# octanis_eps_v05.net
KiCad netlist of a schematic drawn in EAGLE
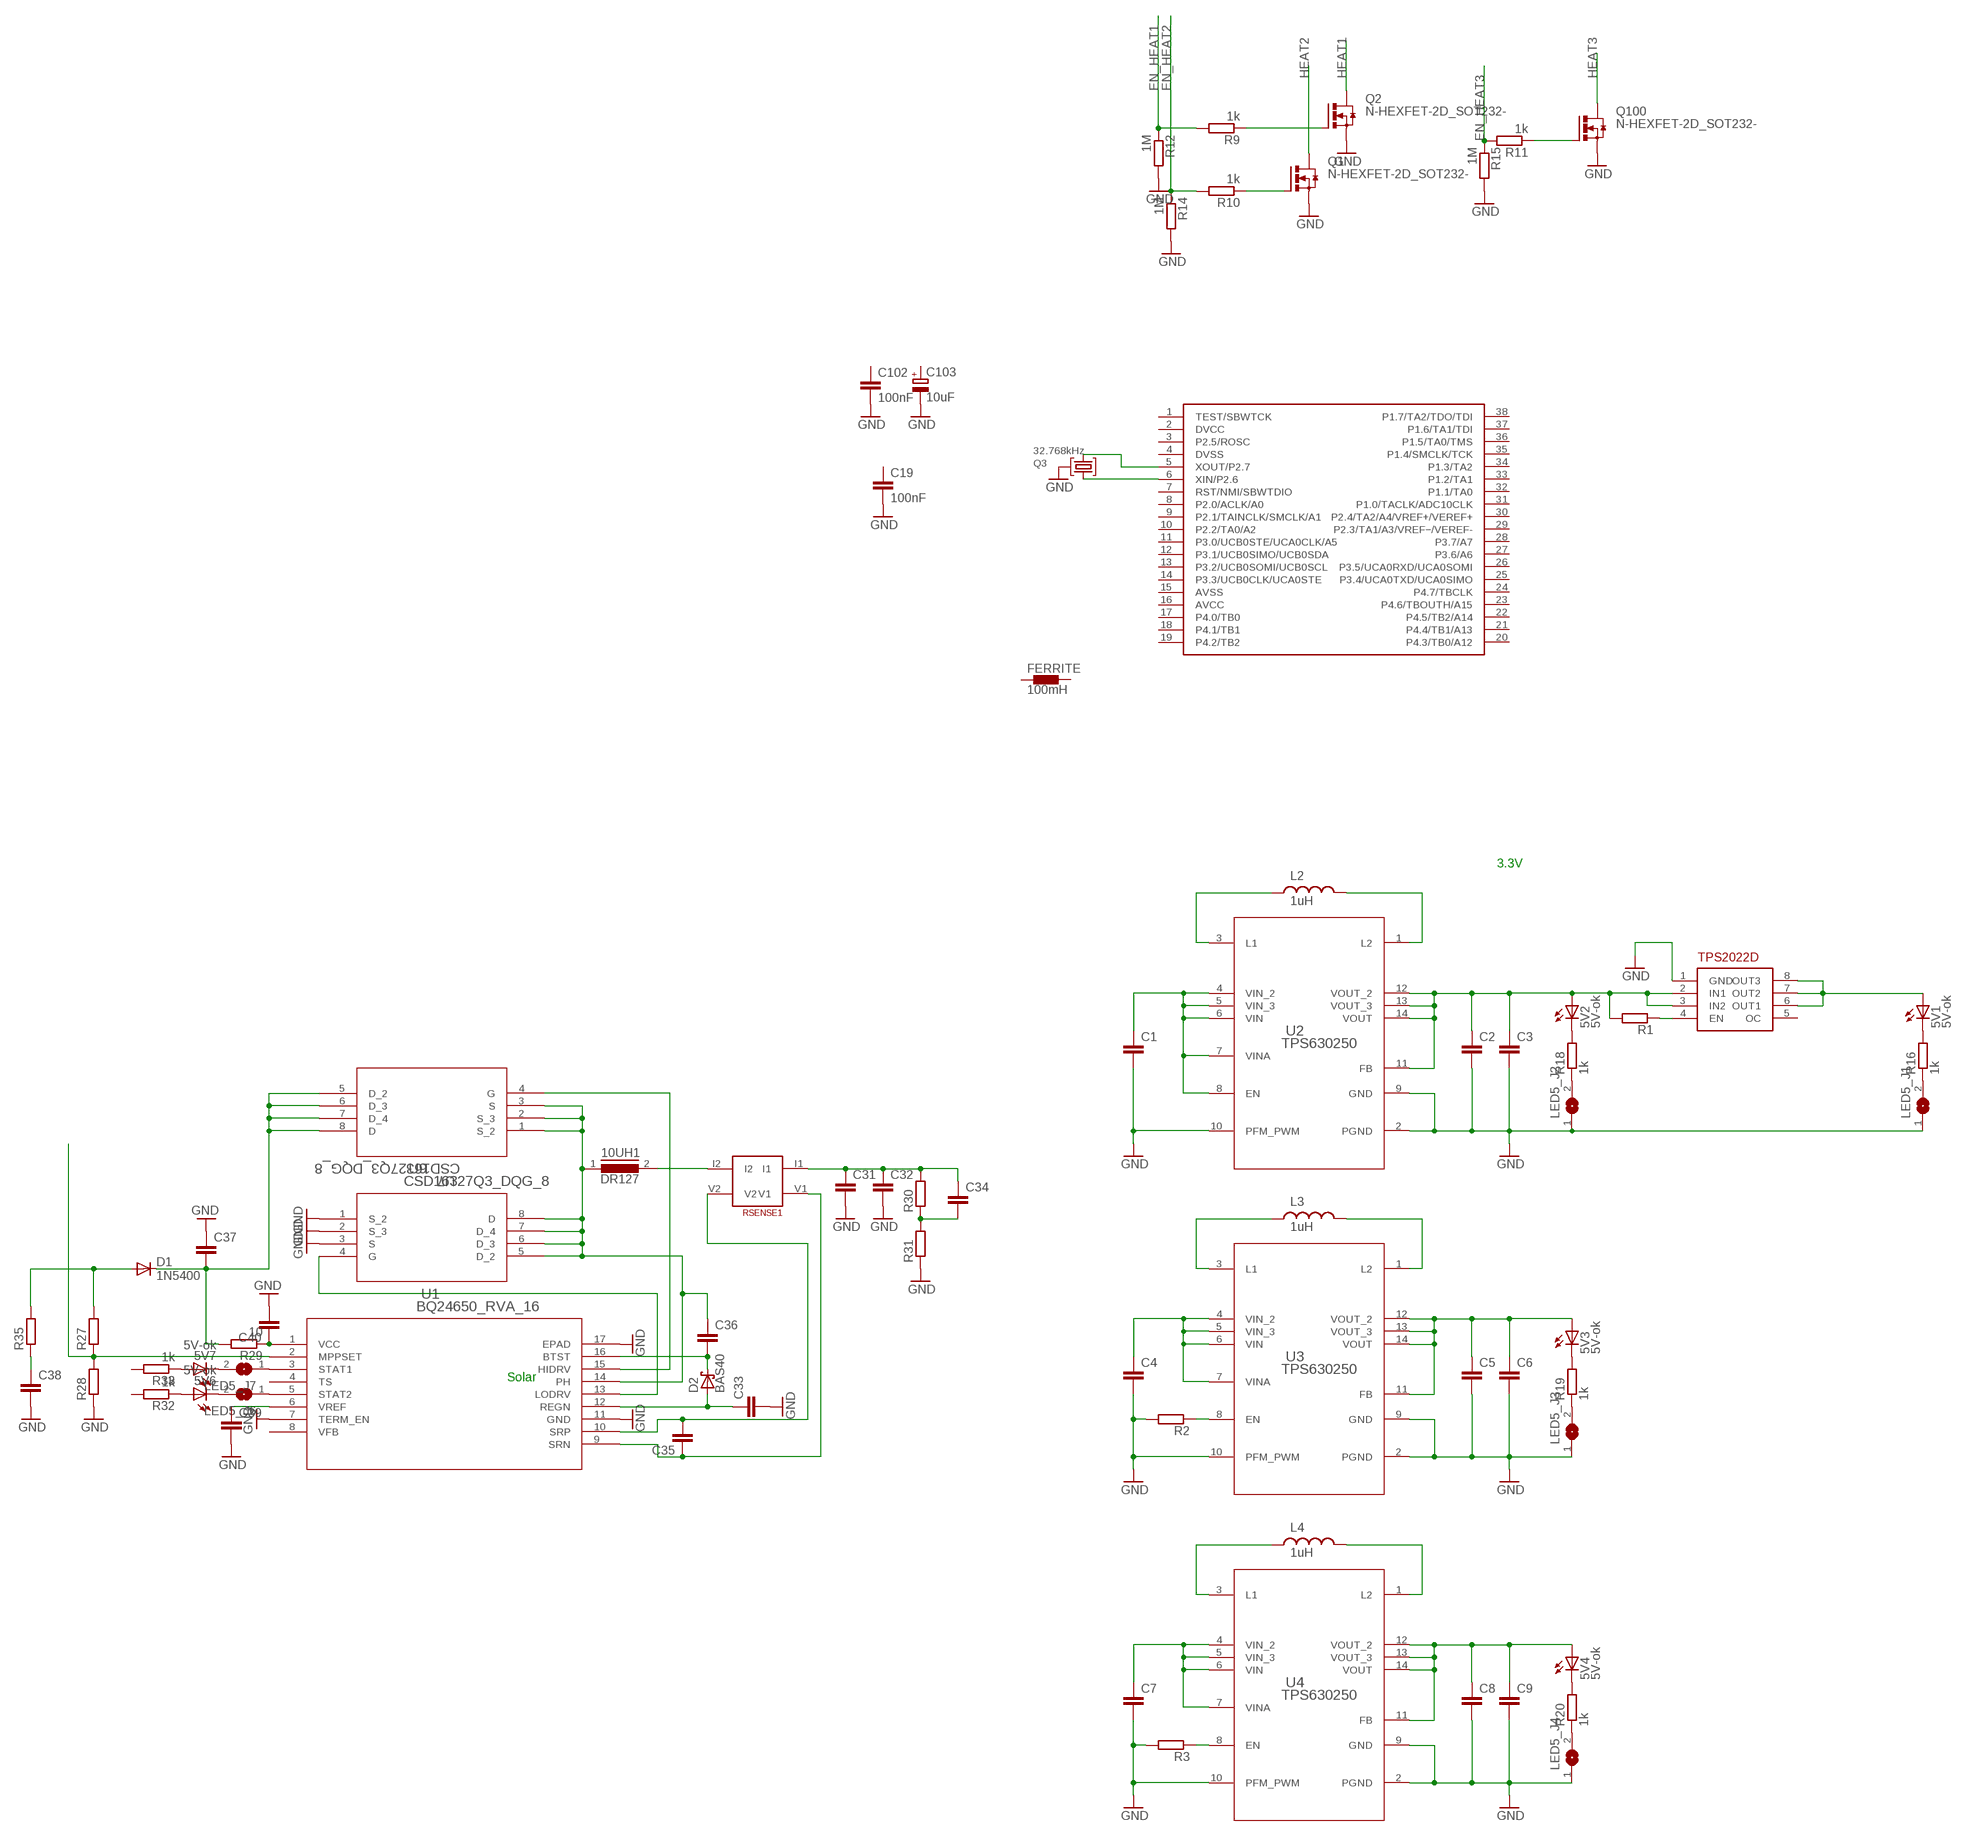
[diagram p0: schematic, sheet 1, part 1 of 2]
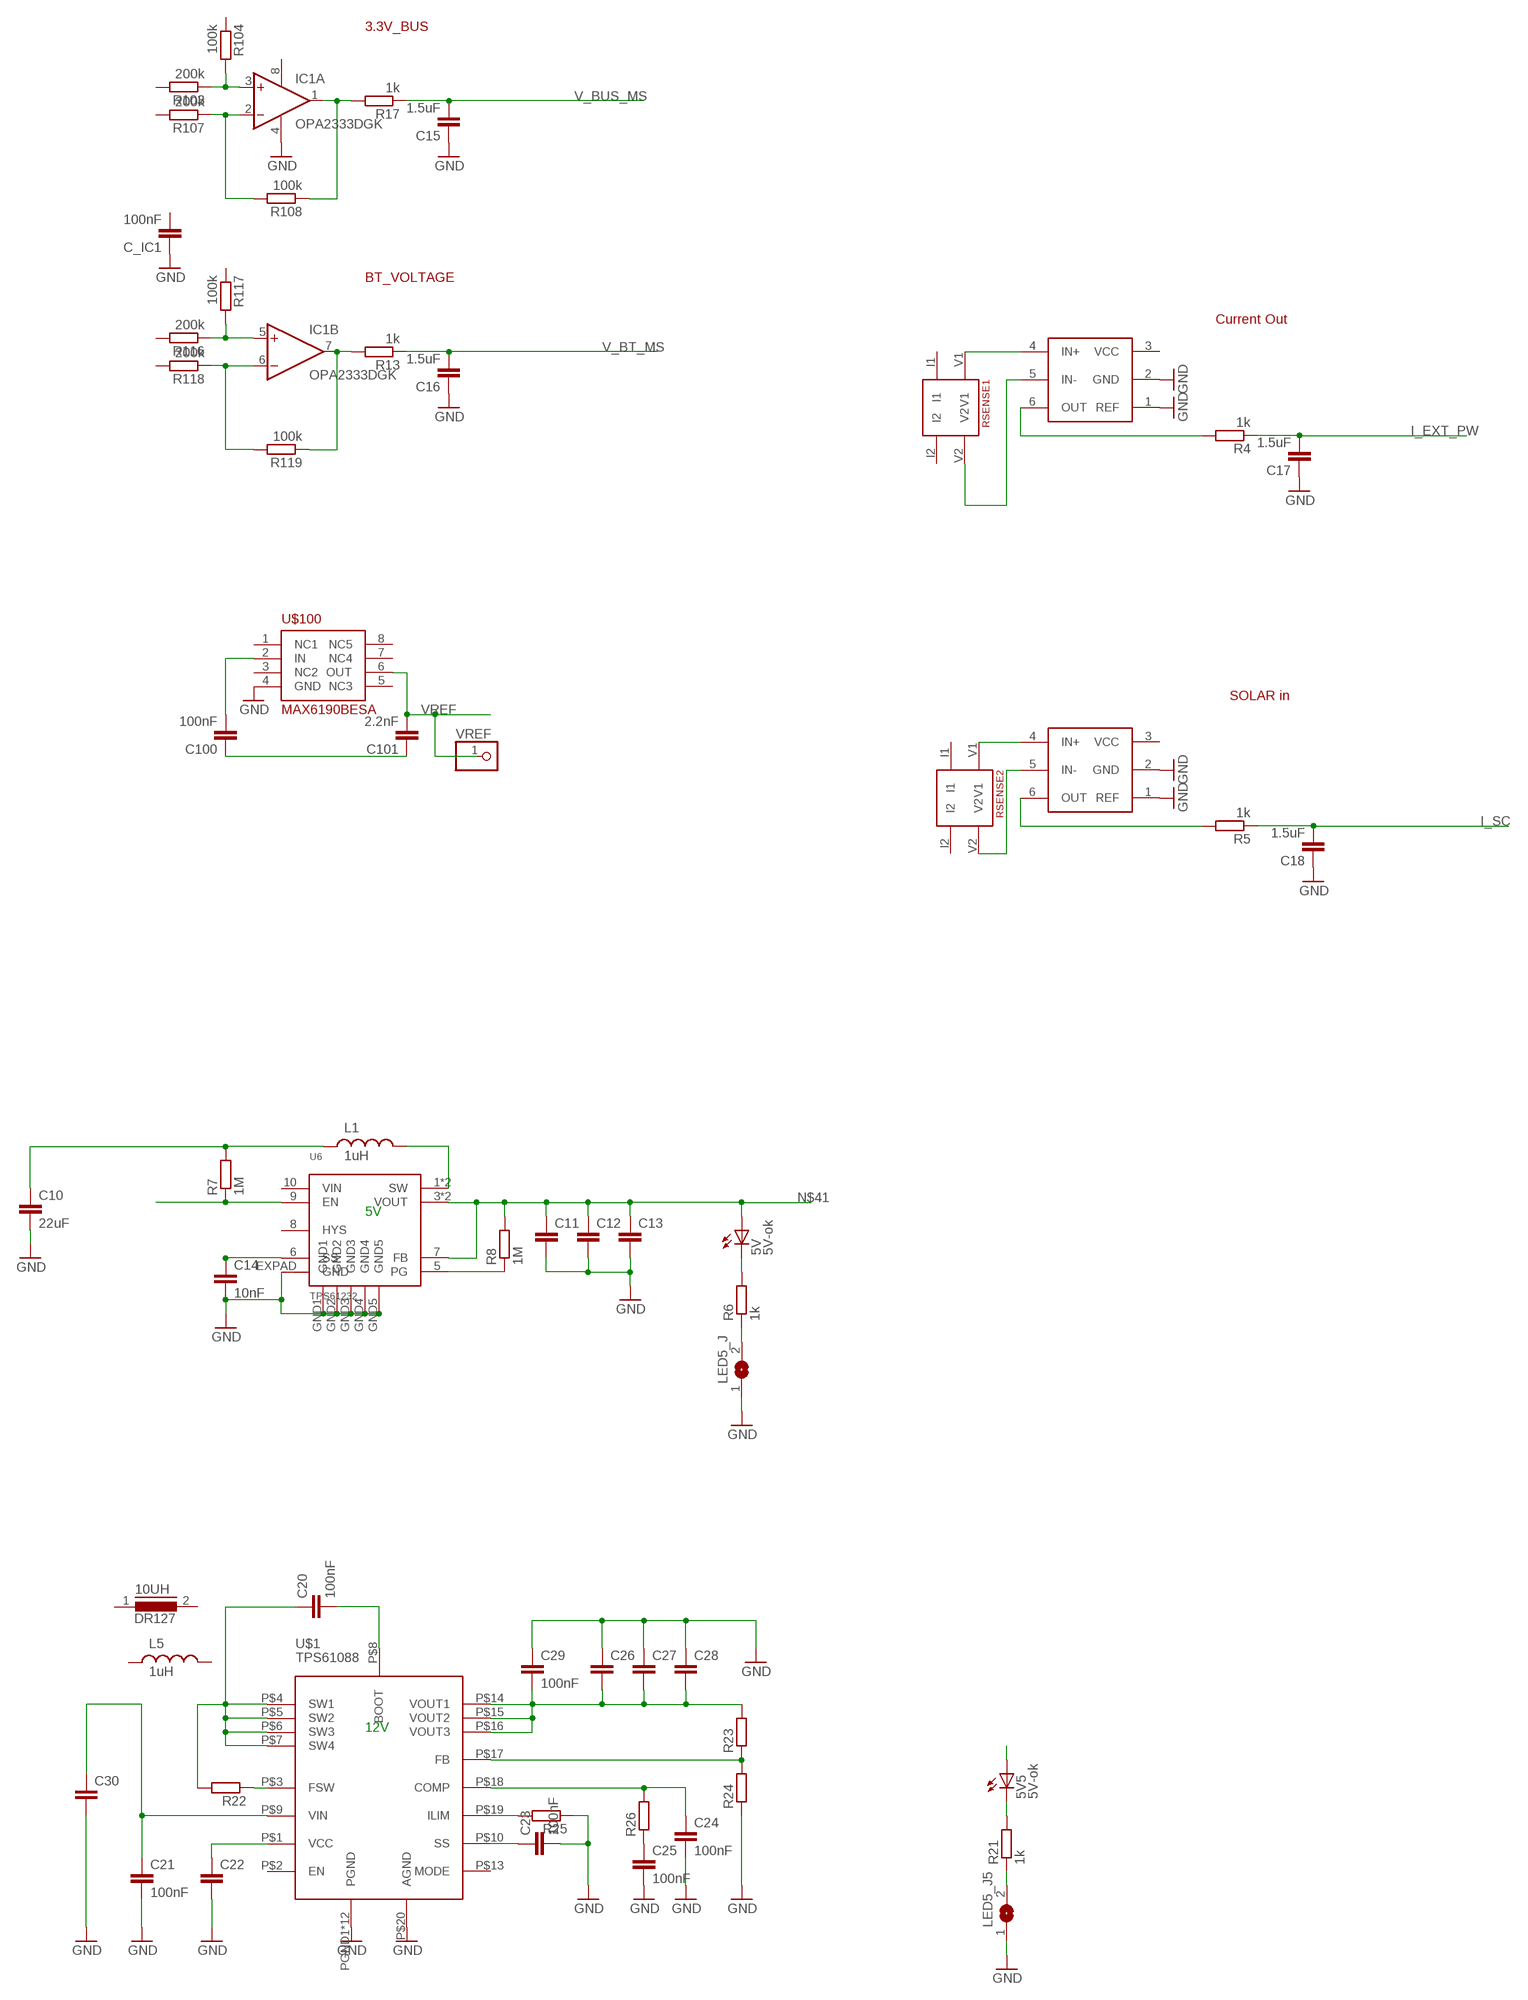
[diagram p1: schematic, sheet 1, part 2 of 2]

(export (version "E")
  (design (tool "Eeschema 10.0.6"))
  (components
    (comp (ref "5V")
      (value "5V-ok")
      (footprint "eagle-import:CHIPLED_0603")
      (libsource (lib "eagle-import") (part "LEDCHIPLED_0603"))
    )
    (comp (ref "5V1")
      (value "5V-ok")
      (footprint "eagle-import:CHIPLED_0603")
      (libsource (lib "eagle-import") (part "LEDCHIPLED_0603"))
    )
    (comp (ref "5V2")
      (value "5V-ok")
      (footprint "eagle-import:CHIPLED_0603")
      (libsource (lib "eagle-import") (part "LEDCHIPLED_0603"))
    )
    (comp (ref "5V3")
      (value "5V-ok")
      (footprint "eagle-import:CHIPLED_0603")
      (libsource (lib "eagle-import") (part "LEDCHIPLED_0603"))
    )
    (comp (ref "5V4")
      (value "5V-ok")
      (footprint "eagle-import:CHIPLED_0603")
      (libsource (lib "eagle-import") (part "LEDCHIPLED_0603"))
    )
    (comp (ref "5V5")
      (value "5V-ok")
      (footprint "eagle-import:CHIPLED_0603")
      (libsource (lib "eagle-import") (part "LEDCHIPLED_0603"))
    )
    (comp (ref "5V6")
      (value "5V-ok")
      (footprint "eagle-import:CHIPLED_0603")
      (libsource (lib "eagle-import") (part "LEDCHIPLED_0603"))
    )
    (comp (ref "5V7")
      (value "5V-ok")
      (footprint "eagle-import:CHIPLED_0603")
      (libsource (lib "eagle-import") (part "LEDCHIPLED_0603"))
    )
    (comp (ref "10UH")
      (value "DR127")
      (footprint "eagle-import:DR127")
      (libsource (lib "eagle-import") (part "DR127"))
    )
    (comp (ref "10UH1")
      (value "DR127")
      (footprint "eagle-import:DR127")
      (libsource (lib "eagle-import") (part "DR127"))
    )
    (comp (ref "C1")
      (value "C-EUC0805")
      (footprint "eagle-import:C0805")
      (libsource (lib "eagle-import") (part "resistor_C-EUC0805"))
    )
    (comp (ref "C2")
      (value "C-EUC0805")
      (footprint "eagle-import:C0805")
      (libsource (lib "eagle-import") (part "resistor_C-EUC0805"))
    )
    (comp (ref "C3")
      (value "C-EUC0805")
      (footprint "eagle-import:C0805")
      (libsource (lib "eagle-import") (part "resistor_C-EUC0805"))
    )
    (comp (ref "C4")
      (value "C-EUC0805")
      (footprint "eagle-import:C0805")
      (libsource (lib "eagle-import") (part "resistor_C-EUC0805"))
    )
    (comp (ref "C5")
      (value "C-EUC0805")
      (footprint "eagle-import:C0805")
      (libsource (lib "eagle-import") (part "resistor_C-EUC0805"))
    )
    (comp (ref "C6")
      (value "C-EUC0805")
      (footprint "eagle-import:C0805")
      (libsource (lib "eagle-import") (part "resistor_C-EUC0805"))
    )
    (comp (ref "C7")
      (value "C-EUC0805")
      (footprint "eagle-import:C0805")
      (libsource (lib "eagle-import") (part "resistor_C-EUC0805"))
    )
    (comp (ref "C8")
      (value "C-EUC0805")
      (footprint "eagle-import:C0805")
      (libsource (lib "eagle-import") (part "resistor_C-EUC0805"))
    )
    (comp (ref "C9")
      (value "C-EUC0805")
      (footprint "eagle-import:C0805")
      (libsource (lib "eagle-import") (part "resistor_C-EUC0805"))
    )
    (comp (ref "C10")
      (value "22uF")
      (footprint "eagle-import:C0603")
      (libsource (lib "eagle-import") (part "C-EUC0603"))
    )
    (comp (ref "C11")
      (value "C-EUC0805")
      (footprint "eagle-import:C0805")
      (libsource (lib "eagle-import") (part "resistor_C-EUC0805"))
    )
    (comp (ref "C12")
      (value "C-EUC0805")
      (footprint "eagle-import:C0805")
      (libsource (lib "eagle-import") (part "resistor_C-EUC0805"))
    )
    (comp (ref "C13")
      (value "C-EUC0805")
      (footprint "eagle-import:C0805")
      (libsource (lib "eagle-import") (part "resistor_C-EUC0805"))
    )
    (comp (ref "C14")
      (value "10nF")
      (footprint "eagle-import:C0603")
      (libsource (lib "eagle-import") (part "C-EUC0603"))
    )
    (comp (ref "C15")
      (value "1.5uF")
      (footprint "eagle-import:C0603")
      (libsource (lib "eagle-import") (part "C-EUC0603"))
    )
    (comp (ref "C16")
      (value "1.5uF")
      (footprint "eagle-import:C0603")
      (libsource (lib "eagle-import") (part "C-EUC0603"))
    )
    (comp (ref "C17")
      (value "1.5uF")
      (footprint "eagle-import:C0603")
      (libsource (lib "eagle-import") (part "C-EUC0603"))
    )
    (comp (ref "C18")
      (value "1.5uF")
      (footprint "eagle-import:C0603")
      (libsource (lib "eagle-import") (part "C-EUC0603"))
    )
    (comp (ref "C19")
      (value "100nF")
      (footprint "eagle-import:C0603")
      (libsource (lib "eagle-import") (part "C-EUC0603"))
    )
    (comp (ref "C20")
      (value "100nF")
      (footprint "eagle-import:C0603")
      (libsource (lib "eagle-import") (part "C-EUC0603"))
    )
    (comp (ref "C21")
      (value "100nF")
      (footprint "eagle-import:C0603")
      (libsource (lib "eagle-import") (part "C-EUC0603"))
    )
    (comp (ref "C22")
      (value "C-EUC0603")
      (footprint "eagle-import:C0603")
      (libsource (lib "eagle-import") (part "C-EUC0603"))
    )
    (comp (ref "C23")
      (value "100nF")
      (footprint "eagle-import:C0603")
      (libsource (lib "eagle-import") (part "C-EUC0603"))
    )
    (comp (ref "C24")
      (value "100nF")
      (footprint "eagle-import:C0603")
      (libsource (lib "eagle-import") (part "C-EUC0603"))
    )
    (comp (ref "C25")
      (value "100nF")
      (footprint "eagle-import:C0603")
      (libsource (lib "eagle-import") (part "C-EUC0603"))
    )
    (comp (ref "C26")
      (value "C-EUC0805")
      (footprint "eagle-import:C0805")
      (libsource (lib "eagle-import") (part "resistor_C-EUC0805"))
    )
    (comp (ref "C27")
      (value "C-EUC0805")
      (footprint "eagle-import:C0805")
      (libsource (lib "eagle-import") (part "resistor_C-EUC0805"))
    )
    (comp (ref "C28")
      (value "C-EUC0805")
      (footprint "eagle-import:C0805")
      (libsource (lib "eagle-import") (part "resistor_C-EUC0805"))
    )
    (comp (ref "C29")
      (value "100nF")
      (footprint "eagle-import:C0603")
      (libsource (lib "eagle-import") (part "C-EUC0603"))
    )
    (comp (ref "C30")
      (value "C-EUC0805")
      (footprint "eagle-import:C0805")
      (libsource (lib "eagle-import") (part "resistor_C-EUC0805"))
    )
    (comp (ref "C31")
      (value "C-EUC0805")
      (footprint "eagle-import:C0805")
      (libsource (lib "eagle-import") (part "resistor_C-EUC0805"))
    )
    (comp (ref "C32")
      (value "C-EUC0805")
      (footprint "eagle-import:C0805")
      (libsource (lib "eagle-import") (part "resistor_C-EUC0805"))
    )
    (comp (ref "C33")
      (value "C-EUC0603")
      (footprint "eagle-import:C0603")
      (libsource (lib "eagle-import") (part "C-EUC0603"))
    )
    (comp (ref "C34")
      (value "C-EUC0603")
      (footprint "eagle-import:C0603")
      (libsource (lib "eagle-import") (part "C-EUC0603"))
    )
    (comp (ref "C35")
      (value "C-EUC0603")
      (footprint "eagle-import:C0603")
      (libsource (lib "eagle-import") (part "C-EUC0603"))
    )
    (comp (ref "C36")
      (value "C-EUC0603")
      (footprint "eagle-import:C0603")
      (libsource (lib "eagle-import") (part "C-EUC0603"))
    )
    (comp (ref "C37")
      (value "C-EUC0805")
      (footprint "eagle-import:C0805")
      (libsource (lib "eagle-import") (part "resistor_C-EUC0805"))
    )
    (comp (ref "C38")
      (value "C-EUC0603")
      (footprint "eagle-import:C0603")
      (libsource (lib "eagle-import") (part "C-EUC0603"))
    )
    (comp (ref "C39")
      (value "C-EUC0603")
      (footprint "eagle-import:C0603")
      (libsource (lib "eagle-import") (part "C-EUC0603"))
    )
    (comp (ref "C40")
      (value "C-EUC0603")
      (footprint "eagle-import:C0603")
      (libsource (lib "eagle-import") (part "C-EUC0603"))
    )
    (comp (ref "C100")
      (value "100nF")
      (footprint "eagle-import:C0603")
      (libsource (lib "eagle-import") (part "C-EUC0603"))
    )
    (comp (ref "C101")
      (value "2.2nF")
      (footprint "eagle-import:C0603")
      (libsource (lib "eagle-import") (part "C-EUC0603"))
    )
    (comp (ref "C102")
      (value "100nF")
      (footprint "eagle-import:C0603")
      (libsource (lib "eagle-import") (part "C-EUC0603"))
    )
    (comp (ref "C103")
      (value "10uF")
      (footprint "eagle-import:A_3216-18R")
      (libsource (lib "eagle-import") (part "CPOL-EUA/3216-18R"))
    )
    (comp (ref "C_IC1")
      (value "100nF")
      (footprint "eagle-import:C0603")
      (libsource (lib "eagle-import") (part "C-EUC0603"))
    )
    (comp (ref "D1")
      (value "1N5400")
      (footprint "eagle-import:DO201-15")
      (libsource (lib "eagle-import") (part "1N5400"))
    )
    (comp (ref "D2")
      (value "BAS40")
      (footprint "eagle-import:SOT23")
      (libsource (lib "eagle-import") (part "BAS40"))
    )
    (comp (ref "FERRITE")
      (value "100mH")
      (footprint "eagle-import:0402")
      (libsource (lib "eagle-import") (part "BLM15HD601SN1"))
    )
    (comp (ref "IC1")
      (value "OPA2333DGK")
      (footprint "eagle-import:MSOP08")
      (libsource (lib "eagle-import") (part "OPA2333DGK"))
    )
    (comp (ref "L1")
      (value "1uH")
      (footprint "eagle-import:XFL4020")
      (libsource (lib "eagle-import") (part "XFL4020"))
    )
    (comp (ref "L2")
      (value "1uH")
      (footprint "eagle-import:XFL4020")
      (libsource (lib "eagle-import") (part "XFL4020"))
    )
    (comp (ref "L3")
      (value "1uH")
      (footprint "eagle-import:XFL4020")
      (libsource (lib "eagle-import") (part "XFL4020"))
    )
    (comp (ref "L4")
      (value "1uH")
      (footprint "eagle-import:XFL4020")
      (libsource (lib "eagle-import") (part "XFL4020"))
    )
    (comp (ref "L5")
      (value "1uH")
      (footprint "eagle-import:XFL4020")
      (libsource (lib "eagle-import") (part "XFL4020"))
    )
    (comp (ref "LED5_J")
      (value "SJ")
      (footprint "eagle-import:SJ")
      (libsource (lib "eagle-import") (part "SJ"))
    )
    (comp (ref "LED5_J1")
      (value "SJ")
      (footprint "eagle-import:SJ")
      (libsource (lib "eagle-import") (part "SJ"))
    )
    (comp (ref "LED5_J2")
      (value "SJ")
      (footprint "eagle-import:SJ")
      (libsource (lib "eagle-import") (part "SJ"))
    )
    (comp (ref "LED5_J3")
      (value "SJ")
      (footprint "eagle-import:SJ")
      (libsource (lib "eagle-import") (part "SJ"))
    )
    (comp (ref "LED5_J4")
      (value "SJ")
      (footprint "eagle-import:SJ")
      (libsource (lib "eagle-import") (part "SJ"))
    )
    (comp (ref "LED5_J5")
      (value "SJ")
      (footprint "eagle-import:SJ")
      (libsource (lib "eagle-import") (part "SJ"))
    )
    (comp (ref "LED5_J6")
      (value "SJ")
      (footprint "eagle-import:SJ")
      (libsource (lib "eagle-import") (part "SJ"))
    )
    (comp (ref "LED5_J7")
      (value "SJ")
      (footprint "eagle-import:SJ")
      (libsource (lib "eagle-import") (part "SJ"))
    )
    (comp (ref "Q1")
      (value "N-HEXFET-2D_SOT232-")
      (footprint "eagle-import:SOT223")
      (libsource (lib "eagle-import") (part "N-HEXFET-2D_?-SOT232"))
    )
    (comp (ref "Q2")
      (value "N-HEXFET-2D_SOT232-")
      (footprint "eagle-import:SOT223")
      (libsource (lib "eagle-import") (part "N-HEXFET-2D_?-SOT232"))
    )
    (comp (ref "Q3")
      (value "32.768kHz")
      (footprint "eagle-import:MS3V-T1R")
      (libsource (lib "eagle-import") (part "MS3V-T1R"))
    )
    (comp (ref "Q100")
      (value "N-HEXFET-2D_SOT232-")
      (footprint "eagle-import:SOT223")
      (libsource (lib "eagle-import") (part "N-HEXFET-2D_?-SOT232"))
    )
    (comp (ref "R1")
      (value "R-EU_R0603")
      (footprint "eagle-import:R0603")
      (libsource (lib "eagle-import") (part "resistor_R-EU_R0603"))
    )
    (comp (ref "R2")
      (value "R-EU_R0603")
      (footprint "eagle-import:R0603")
      (libsource (lib "eagle-import") (part "resistor_R-EU_R0603"))
    )
    (comp (ref "R3")
      (value "R-EU_R0603")
      (footprint "eagle-import:R0603")
      (libsource (lib "eagle-import") (part "resistor_R-EU_R0603"))
    )
    (comp (ref "R4")
      (value "1k")
      (footprint "eagle-import:R0603")
      (libsource (lib "eagle-import") (part "R-EU_R0603"))
    )
    (comp (ref "R5")
      (value "1k")
      (footprint "eagle-import:R0603")
      (libsource (lib "eagle-import") (part "R-EU_R0603"))
    )
    (comp (ref "R6")
      (value "1k")
      (footprint "eagle-import:R0603")
      (libsource (lib "eagle-import") (part "R-EU_R0603"))
    )
    (comp (ref "R7")
      (value "1M")
      (footprint "eagle-import:R0603")
      (libsource (lib "eagle-import") (part "R-EU_R0603"))
    )
    (comp (ref "R8")
      (value "1M")
      (footprint "eagle-import:R0603")
      (libsource (lib "eagle-import") (part "R-EU_R0603"))
    )
    (comp (ref "R9")
      (value "1k")
      (footprint "eagle-import:R0603")
      (libsource (lib "eagle-import") (part "R-EU_R0603"))
    )
    (comp (ref "R10")
      (value "1k")
      (footprint "eagle-import:R0603")
      (libsource (lib "eagle-import") (part "R-EU_R0603"))
    )
    (comp (ref "R11")
      (value "1k")
      (footprint "eagle-import:R0603")
      (libsource (lib "eagle-import") (part "R-EU_R0603"))
    )
    (comp (ref "R12")
      (value "1M")
      (footprint "eagle-import:R0603")
      (libsource (lib "eagle-import") (part "R-EU_R0603"))
    )
    (comp (ref "R13")
      (value "1k")
      (footprint "eagle-import:R0603")
      (libsource (lib "eagle-import") (part "R-EU_R0603"))
    )
    (comp (ref "R14")
      (value "1M")
      (footprint "eagle-import:R0603")
      (libsource (lib "eagle-import") (part "R-EU_R0603"))
    )
    (comp (ref "R15")
      (value "1M")
      (footprint "eagle-import:R0603")
      (libsource (lib "eagle-import") (part "R-EU_R0603"))
    )
    (comp (ref "R16")
      (value "1k")
      (footprint "eagle-import:R0603")
      (libsource (lib "eagle-import") (part "R-EU_R0603"))
    )
    (comp (ref "R17")
      (value "1k")
      (footprint "eagle-import:R0603")
      (libsource (lib "eagle-import") (part "R-EU_R0603"))
    )
    (comp (ref "R18")
      (value "1k")
      (footprint "eagle-import:R0603")
      (libsource (lib "eagle-import") (part "R-EU_R0603"))
    )
    (comp (ref "R19")
      (value "1k")
      (footprint "eagle-import:R0603")
      (libsource (lib "eagle-import") (part "R-EU_R0603"))
    )
    (comp (ref "R20")
      (value "1k")
      (footprint "eagle-import:R0603")
      (libsource (lib "eagle-import") (part "R-EU_R0603"))
    )
    (comp (ref "R21")
      (value "1k")
      (footprint "eagle-import:R0603")
      (libsource (lib "eagle-import") (part "R-EU_R0603"))
    )
    (comp (ref "R22")
      (value "R-EU_R0603")
      (footprint "eagle-import:R0603")
      (libsource (lib "eagle-import") (part "resistor_R-EU_R0603"))
    )
    (comp (ref "R23")
      (value "R-EU_R0603")
      (footprint "eagle-import:R0603")
      (libsource (lib "eagle-import") (part "resistor_R-EU_R0603"))
    )
    (comp (ref "R24")
      (value "R-EU_R0603")
      (footprint "eagle-import:R0603")
      (libsource (lib "eagle-import") (part "resistor_R-EU_R0603"))
    )
    (comp (ref "R25")
      (value "R-EU_R0603")
      (footprint "eagle-import:R0603")
      (libsource (lib "eagle-import") (part "resistor_R-EU_R0603"))
    )
    (comp (ref "R26")
      (value "R-EU_R0603")
      (footprint "eagle-import:R0603")
      (libsource (lib "eagle-import") (part "resistor_R-EU_R0603"))
    )
    (comp (ref "R27")
      (value "R-EU_R0603")
      (footprint "eagle-import:R0603")
      (libsource (lib "eagle-import") (part "R-EU_R0603"))
    )
    (comp (ref "R28")
      (value "R-EU_R0603")
      (footprint "eagle-import:R0603")
      (libsource (lib "eagle-import") (part "R-EU_R0603"))
    )
    (comp (ref "R29")
      (value "10")
      (footprint "eagle-import:R0603")
      (libsource (lib "eagle-import") (part "R-EU_R0603"))
    )
    (comp (ref "R30")
      (value "R-EU_R0603")
      (footprint "eagle-import:R0603")
      (libsource (lib "eagle-import") (part "R-EU_R0603"))
    )
    (comp (ref "R31")
      (value "R-EU_R0603")
      (footprint "eagle-import:R0603")
      (libsource (lib "eagle-import") (part "R-EU_R0603"))
    )
    (comp (ref "R32")
      (value "1k")
      (footprint "eagle-import:R0603")
      (libsource (lib "eagle-import") (part "R-EU_R0603"))
    )
    (comp (ref "R33")
      (value "1k")
      (footprint "eagle-import:R0603")
      (libsource (lib "eagle-import") (part "R-EU_R0603"))
    )
    (comp (ref "R35")
      (value "R-EU_R0603")
      (footprint "eagle-import:R0603")
      (libsource (lib "eagle-import") (part "R-EU_R0603"))
    )
    (comp (ref "R103")
      (value "200k")
      (footprint "eagle-import:R0603")
      (libsource (lib "eagle-import") (part "R-EU_R0603"))
    )
    (comp (ref "R104")
      (value "100k")
      (footprint "eagle-import:R0603")
      (libsource (lib "eagle-import") (part "R-EU_R0603"))
    )
    (comp (ref "R107")
      (value "200k")
      (footprint "eagle-import:R0603")
      (libsource (lib "eagle-import") (part "R-EU_R0603"))
    )
    (comp (ref "R108")
      (value "100k")
      (footprint "eagle-import:R0603")
      (libsource (lib "eagle-import") (part "R-EU_R0603"))
    )
    (comp (ref "R116")
      (value "200k")
      (footprint "eagle-import:R0603")
      (libsource (lib "eagle-import") (part "R-EU_R0603"))
    )
    (comp (ref "R117")
      (value "100k")
      (footprint "eagle-import:R0603")
      (libsource (lib "eagle-import") (part "R-EU_R0603"))
    )
    (comp (ref "R118")
      (value "200k")
      (footprint "eagle-import:R0603")
      (libsource (lib "eagle-import") (part "R-EU_R0603"))
    )
    (comp (ref "R119")
      (value "100k")
      (footprint "eagle-import:R0603")
      (libsource (lib "eagle-import") (part "R-EU_R0603"))
    )
    (comp (ref "RSENSE1")
      (value "RSENSE2")
      (footprint "eagle-import:4PADS_RESISTOR")
      (libsource (lib "eagle-import") (part "CURRENT_RESISTOR"))
    )
    (comp (ref "R_SENSE1")
      (value "RSENSE1")
      (footprint "eagle-import:4PADS_RESISTOR")
      (libsource (lib "eagle-import") (part "CURRENT_RESISTOR"))
    )
    (comp (ref "R_SENSE2")
      (value "RSENSE1")
      (footprint "eagle-import:4PADS_RESISTOR")
      (libsource (lib "eagle-import") (part "CURRENT_RESISTOR"))
    )
    (comp (ref "U$1")
      (value "TPS61088")
      (footprint "eagle-import:R-PVQFN-N20")
      (libsource (lib "eagle-import") (part "TPS61088"))
    )
    (comp (ref "U$2")
      (value "INA213")
      (footprint "eagle-import:SC70-6")
      (libsource (lib "eagle-import") (part "INA213"))
    )
    (comp (ref "U$3")
      (value "INA213")
      (footprint "eagle-import:SC70-6")
      (libsource (lib "eagle-import") (part "INA213"))
    )
    (comp (ref "U$100")
      (value "MAX6190BESA")
      (footprint "eagle-import:SO8")
      (libsource (lib "eagle-import") (part "MAX6190BESA"))
    )
    (comp (ref "U1")
      (value "BQ24650_RVA_16")
      (footprint "eagle-import:RVA16_2P14X2P14")
      (fields
        (field (name "GENERIC_PART_NUMBER") "BQ24650")
        (field (name "MANUFACTURER") "Texas Instruments")
      )
      (libsource (lib "eagle-import") (part "BQ24650_RVA_16"))
    )
    (comp (ref "U2")
      (value "TPS630250")
      (footprint "eagle-import:RNC0014A")
      (fields
        (field (name "ALTERNATEPARTNUMBER") "TPS630250RNCT")
        (field (name "MANUFACTURER") "Texas Instruments")
        (field (name "PARTNUMBER") "TPS630250RNCR")
      )
      (libsource (lib "eagle-import") (part "TPS630250RNCR"))
    )
    (comp (ref "U3")
      (value "TPS630250")
      (footprint "eagle-import:RNC0014A")
      (fields
        (field (name "ALTERNATEPARTNUMBER") "TPS630250RNCT")
        (field (name "MANUFACTURER") "Texas Instruments")
        (field (name "PARTNUMBER") "TPS630250RNCR")
      )
      (libsource (lib "eagle-import") (part "TPS630250RNCR"))
    )
    (comp (ref "U4")
      (value "TPS630250")
      (footprint "eagle-import:RNC0014A")
      (fields
        (field (name "ALTERNATEPARTNUMBER") "TPS630250RNCT")
        (field (name "MANUFACTURER") "Texas Instruments")
        (field (name "PARTNUMBER") "TPS630250RNCR")
      )
      (libsource (lib "eagle-import") (part "TPS630250RNCR"))
    )
    (comp (ref "U5")
      (value "TPS2022D")
      (footprint "eagle-import:SO8")
      (libsource (lib "eagle-import") (part "TPS2022D"))
    )
    (comp (ref "U6")
      (value "TPS61232")
      (footprint "eagle-import:S-PVSON-N10")
      (libsource (lib "eagle-import") (part "TPS61232"))
    )
    (comp (ref "U7")
      (value "CSD16327Q3_DQG_8")
      (footprint "eagle-import:DQG8")
      (fields
        (field (name "GENERIC_PART_NUMBER") "CSD16327Q3")
        (field (name "MANUFACTURER") "Texas Instruments")
      )
      (libsource (lib "eagle-import") (part "CSD16327Q3_DQG_8"))
    )
    (comp (ref "U8")
      (value "MSP430G2544")
      (footprint "eagle-import:TSSOP38_MSPGXX44_SERIES")
      (libsource (lib "eagle-import") (part "MSP430G2544"))
    )
    (comp (ref "U9")
      (value "CSD16327Q3_DQG_8")
      (footprint "eagle-import:DQG8")
      (fields
        (field (name "GENERIC_PART_NUMBER") "CSD16327Q3")
        (field (name "MANUFACTURER") "Texas Instruments")
      )
      (libsource (lib "eagle-import") (part "CSD16327Q3_DQG_8"))
    )
    (comp (ref "VREF")
      (value "PINHD-1X1")
      (footprint "eagle-import:1X01")
      (libsource (lib "eagle-import") (part "PINHD-1X1"))
    )
  )
  (nets
    (net (code "1") (name "/EN_HEAT1") (class "Default")
      (node (ref "R12") (pin "1") (pinfunction "1_1") (pintype "passive"))
      (node (ref "R9") (pin "2") (pinfunction "2_2") (pintype "passive"))
    )
    (net (code "2") (name "/EN_HEAT2") (class "Default")
      (node (ref "R10") (pin "2") (pinfunction "2_2") (pintype "passive"))
      (node (ref "R14") (pin "1") (pinfunction "1_1") (pintype "passive"))
    )
    (net (code "3") (name "/EN_HEAT3") (class "Default")
      (node (ref "R11") (pin "2") (pinfunction "2_2") (pintype "passive"))
      (node (ref "R15") (pin "1") (pinfunction "1_1") (pintype "passive"))
    )
    (net (code "4") (name "/HEAT1") (class "Default")
      (node (ref "Q2") (pin "2") (pinfunction "D_2") (pintype "passive"))
      (node (ref "Q2") (pin "4") (pinfunction "D_4") (pintype "passive"))
    )
    (net (code "5") (name "/HEAT2") (class "Default")
      (node (ref "Q1") (pin "2") (pinfunction "D_2") (pintype "passive"))
      (node (ref "Q1") (pin "4") (pinfunction "D_4") (pintype "passive"))
    )
    (net (code "6") (name "/HEAT3") (class "Default")
      (node (ref "Q100") (pin "2") (pinfunction "D_2") (pintype "passive"))
      (node (ref "Q100") (pin "4") (pinfunction "D_4") (pintype "passive"))
    )
    (net (code "7") (name "/I_EXT_PW") (class "Default")
      (node (ref "C17") (pin "2") (pinfunction "2_2") (pintype "passive"))
      (node (ref "R4") (pin "1") (pinfunction "1_1") (pintype "passive"))
    )
    (net (code "8") (name "/I_SC") (class "Default")
      (node (ref "C18") (pin "2") (pinfunction "2_2") (pintype "passive"))
      (node (ref "R5") (pin "1") (pinfunction "1_1") (pintype "passive"))
    )
    (net (code "9") (name "/N$41") (class "Default")
      (node (ref "5V") (pin "A") (pinfunction "A_A") (pintype "passive"))
      (node (ref "C11") (pin "1") (pinfunction "1_1") (pintype "passive"))
      (node (ref "C12") (pin "1") (pinfunction "1_1") (pintype "passive"))
      (node (ref "C13") (pin "1") (pinfunction "1_1") (pintype "passive"))
      (node (ref "R8") (pin "2") (pinfunction "2_2") (pintype "passive"))
      (node (ref "U6") (pin "3") (pinfunction "VOUT_3") (pintype "power_in"))
      (node (ref "U6") (pin "4") (pinfunction "VOUT_4") (pintype "power_in"))
      (node (ref "U6") (pin "7") (pinfunction "FB_7") (pintype "input"))
    )
    (net (code "10") (name "/V+") (class "Default")
      (node (ref "IC1") (pin "8") (pinfunction "V+_8") (pintype "power_in"))
    )
    (net (code "11") (name "/VREF") (class "Default")
      (node (ref "C101") (pin "2") (pinfunction "2_2") (pintype "passive"))
      (node (ref "U$100") (pin "6") (pinfunction "OUT_6") (pintype "bidirectional"))
      (node (ref "VREF") (pin "1") (pinfunction "1_1") (pintype "passive"))
    )
    (net (code "12") (name "/V_BT_MS") (class "Default")
      (node (ref "C16") (pin "2") (pinfunction "2_2") (pintype "passive"))
      (node (ref "R13") (pin "1") (pinfunction "1_1") (pintype "passive"))
    )
    (net (code "13") (name "/V_BUS_MS") (class "Default")
      (node (ref "C15") (pin "2") (pinfunction "2_2") (pintype "passive"))
      (node (ref "R17") (pin "1") (pinfunction "1_1") (pintype "passive"))
    )
    (net (code "14") (name "GND") (class "Default")
      (node (ref "C1") (pin "2") (pinfunction "2_2") (pintype "passive"))
      (node (ref "C10") (pin "2") (pinfunction "2_2") (pintype "passive"))
      (node (ref "C102") (pin "2") (pinfunction "2_2") (pintype "passive"))
      (node (ref "C103") (pin "-") (pinfunction "-_-") (pintype "passive"))
      (node (ref "C11") (pin "2") (pinfunction "2_2") (pintype "passive"))
      (node (ref "C12") (pin "2") (pinfunction "2_2") (pintype "passive"))
      (node (ref "C13") (pin "2") (pinfunction "2_2") (pintype "passive"))
      (node (ref "C14") (pin "2") (pinfunction "2_2") (pintype "passive"))
      (node (ref "C15") (pin "1") (pinfunction "1_1") (pintype "passive"))
      (node (ref "C16") (pin "1") (pinfunction "1_1") (pintype "passive"))
      (node (ref "C17") (pin "1") (pinfunction "1_1") (pintype "passive"))
      (node (ref "C18") (pin "1") (pinfunction "1_1") (pintype "passive"))
      (node (ref "C19") (pin "2") (pinfunction "2_2") (pintype "passive"))
      (node (ref "C2") (pin "2") (pinfunction "2_2") (pintype "passive"))
      (node (ref "C21") (pin "2") (pinfunction "2_2") (pintype "passive"))
      (node (ref "C22") (pin "2") (pinfunction "2_2") (pintype "passive"))
      (node (ref "C23") (pin "2") (pinfunction "2_2") (pintype "passive"))
      (node (ref "C24") (pin "2") (pinfunction "2_2") (pintype "passive"))
      (node (ref "C25") (pin "2") (pinfunction "2_2") (pintype "passive"))
      (node (ref "C26") (pin "1") (pinfunction "1_1") (pintype "passive"))
      (node (ref "C27") (pin "1") (pinfunction "1_1") (pintype "passive"))
      (node (ref "C28") (pin "1") (pinfunction "1_1") (pintype "passive"))
      (node (ref "C29") (pin "1") (pinfunction "1_1") (pintype "passive"))
      (node (ref "C3") (pin "2") (pinfunction "2_2") (pintype "passive"))
      (node (ref "C30") (pin "2") (pinfunction "2_2") (pintype "passive"))
      (node (ref "C31") (pin "2") (pinfunction "2_2") (pintype "passive"))
      (node (ref "C32") (pin "2") (pinfunction "2_2") (pintype "passive"))
      (node (ref "C33") (pin "2") (pinfunction "2_2") (pintype "passive"))
      (node (ref "C37") (pin "1") (pinfunction "1_1") (pintype "passive"))
      (node (ref "C38") (pin "2") (pinfunction "2_2") (pintype "passive"))
      (node (ref "C39") (pin "2") (pinfunction "2_2") (pintype "passive"))
      (node (ref "C4") (pin "2") (pinfunction "2_2") (pintype "passive"))
      (node (ref "C40") (pin "2") (pinfunction "2_2") (pintype "passive"))
      (node (ref "C5") (pin "2") (pinfunction "2_2") (pintype "passive"))
      (node (ref "C6") (pin "2") (pinfunction "2_2") (pintype "passive"))
      (node (ref "C7") (pin "2") (pinfunction "2_2") (pintype "passive"))
      (node (ref "C8") (pin "2") (pinfunction "2_2") (pintype "passive"))
      (node (ref "C9") (pin "2") (pinfunction "2_2") (pintype "passive"))
      (node (ref "C_IC1") (pin "1") (pinfunction "1_1") (pintype "passive"))
      (node (ref "IC1") (pin "4") (pinfunction "V-_4") (pintype "power_in"))
      (node (ref "LED5_J") (pin "1") (pinfunction "1_1") (pintype "passive"))
      (node (ref "LED5_J1") (pin "1") (pinfunction "1_1") (pintype "passive"))
      (node (ref "LED5_J2") (pin "1") (pinfunction "1_1") (pintype "passive"))
      (node (ref "LED5_J3") (pin "1") (pinfunction "1_1") (pintype "passive"))
      (node (ref "LED5_J4") (pin "1") (pinfunction "1_1") (pintype "passive"))
      (node (ref "LED5_J5") (pin "1") (pinfunction "1_1") (pintype "passive"))
      (node (ref "Q1") (pin "3") (pinfunction "S_3") (pintype "passive"))
      (node (ref "Q100") (pin "3") (pinfunction "S_3") (pintype "passive"))
      (node (ref "Q2") (pin "3") (pinfunction "S_3") (pintype "passive"))
      (node (ref "Q3") (pin "P3") (pinfunction "GND_P3") (pintype "power_in"))
      (node (ref "R12") (pin "2") (pinfunction "2_2") (pintype "passive"))
      (node (ref "R14") (pin "2") (pinfunction "2_2") (pintype "passive"))
      (node (ref "R15") (pin "2") (pinfunction "2_2") (pintype "passive"))
      (node (ref "R2") (pin "2") (pinfunction "2_2") (pintype "passive"))
      (node (ref "R24") (pin "1") (pinfunction "1_1") (pintype "passive"))
      (node (ref "R25") (pin "1") (pinfunction "1_1") (pintype "passive"))
      (node (ref "R28") (pin "1") (pinfunction "1_1") (pintype "passive"))
      (node (ref "R3") (pin "2") (pinfunction "2_2") (pintype "passive"))
      (node (ref "R31") (pin "1") (pinfunction "1_1") (pintype "passive"))
      (node (ref "U$1") (pin "P$20") (pinfunction "AGND_P$20") (pintype "bidirectional"))
      (node (ref "U$1") (pin "PGND1") (pinfunction "PGND_PGND1") (pintype "bidirectional"))
      (node (ref "U$1") (pin "PGND10") (pinfunction "PGND_PGND10") (pintype "bidirectional"))
      (node (ref "U$1") (pin "PGND11") (pinfunction "PGND_PGND11") (pintype "bidirectional"))
      (node (ref "U$1") (pin "PGND12") (pinfunction "PGND_PGND12") (pintype "bidirectional"))
      (node (ref "U$1") (pin "PGND2") (pinfunction "PGND_PGND2") (pintype "bidirectional"))
      (node (ref "U$1") (pin "PGND3") (pinfunction "PGND_PGND3") (pintype "bidirectional"))
      (node (ref "U$1") (pin "PGND4") (pinfunction "PGND_PGND4") (pintype "bidirectional"))
      (node (ref "U$1") (pin "PGND5") (pinfunction "PGND_PGND5") (pintype "bidirectional"))
      (node (ref "U$1") (pin "PGND6") (pinfunction "PGND_PGND6") (pintype "bidirectional"))
      (node (ref "U$1") (pin "PGND7") (pinfunction "PGND_PGND7") (pintype "bidirectional"))
      (node (ref "U$1") (pin "PGND8") (pinfunction "PGND_PGND8") (pintype "bidirectional"))
      (node (ref "U$1") (pin "PGND9") (pinfunction "PGND_PGND9") (pintype "bidirectional"))
      (node (ref "U$100") (pin "4") (pinfunction "GND_4") (pintype "bidirectional"))
      (node (ref "U$2") (pin "1") (pinfunction "REF_1") (pintype "bidirectional"))
      (node (ref "U$2") (pin "2") (pinfunction "GND_2") (pintype "bidirectional"))
      (node (ref "U$3") (pin "1") (pinfunction "REF_1") (pintype "bidirectional"))
      (node (ref "U$3") (pin "2") (pinfunction "GND_2") (pintype "bidirectional"))
      (node (ref "U1") (pin "11") (pinfunction "GND_11") (pintype "power_in"))
      (node (ref "U1") (pin "17") (pinfunction "EPAD_17") (pintype "power_in"))
      (node (ref "U1") (pin "7") (pinfunction "TERM_EN_7") (pintype "input"))
      (node (ref "U2") (pin "10") (pinfunction "PFM_PWM_10") (pintype "input"))
      (node (ref "U2") (pin "2") (pinfunction "PGND_2") (pintype "power_in"))
      (node (ref "U2") (pin "9") (pinfunction "GND_9") (pintype "power_in"))
      (node (ref "U3") (pin "10") (pinfunction "PFM_PWM_10") (pintype "input"))
      (node (ref "U3") (pin "2") (pinfunction "PGND_2") (pintype "power_in"))
      (node (ref "U3") (pin "9") (pinfunction "GND_9") (pintype "power_in"))
      (node (ref "U4") (pin "10") (pinfunction "PFM_PWM_10") (pintype "input"))
      (node (ref "U4") (pin "2") (pinfunction "PGND_2") (pintype "power_in"))
      (node (ref "U4") (pin "9") (pinfunction "GND_9") (pintype "power_in"))
      (node (ref "U5") (pin "1") (pinfunction "GND_1") (pintype "bidirectional"))
      (node (ref "U6") (pin "EXPAD") (pinfunction "GND_EXPAD") (pintype "power_in"))
      (node (ref "U6") (pin "GND1") (pinfunction "GND1_GND1") (pintype "power_in"))
      (node (ref "U6") (pin "GND2") (pinfunction "GND2_GND2") (pintype "power_in"))
      (node (ref "U6") (pin "GND3") (pinfunction "GND3_GND3") (pintype "power_in"))
      (node (ref "U6") (pin "GND4") (pinfunction "GND4_GND4") (pintype "power_in"))
      (node (ref "U6") (pin "GND5") (pinfunction "GND5_GND5") (pintype "power_in"))
      (node (ref "U9") (pin "1") (pinfunction "S_2_1") (pintype "passive"))
      (node (ref "U9") (pin "2") (pinfunction "S_3_2") (pintype "passive"))
      (node (ref "U9") (pin "3") (pinfunction "S_3") (pintype "passive"))
    )
    (net (code "15") (name "Net-(5V-PadC)") (class "Default")
      (node (ref "5V") (pin "C") (pinfunction "C_C") (pintype "passive"))
      (node (ref "R6") (pin "2") (pinfunction "2_2") (pintype "passive"))
    )
    (net (code "16") (name "Net-(5V1-PadC)") (class "Default")
      (node (ref "5V1") (pin "C") (pinfunction "C_C") (pintype "passive"))
      (node (ref "R16") (pin "2") (pinfunction "2_2") (pintype "passive"))
    )
    (net (code "17") (name "Net-(5V2-PadC)") (class "Default")
      (node (ref "5V2") (pin "C") (pinfunction "C_C") (pintype "passive"))
      (node (ref "R18") (pin "2") (pinfunction "2_2") (pintype "passive"))
    )
    (net (code "18") (name "Net-(5V3-PadC)") (class "Default")
      (node (ref "5V3") (pin "C") (pinfunction "C_C") (pintype "passive"))
      (node (ref "R19") (pin "2") (pinfunction "2_2") (pintype "passive"))
    )
    (net (code "19") (name "Net-(5V4-PadC)") (class "Default")
      (node (ref "5V4") (pin "C") (pinfunction "C_C") (pintype "passive"))
      (node (ref "R20") (pin "2") (pinfunction "2_2") (pintype "passive"))
    )
    (net (code "20") (name "Net-(5V5-PadC)") (class "Default")
      (node (ref "5V5") (pin "C") (pinfunction "C_C") (pintype "passive"))
      (node (ref "R21") (pin "2") (pinfunction "2_2") (pintype "passive"))
    )
    (net (code "21") (name "Net-(5V6-PadA)") (class "Default")
      (node (ref "5V6") (pin "A") (pinfunction "A_A") (pintype "passive"))
      (node (ref "R32") (pin "1") (pinfunction "1_1") (pintype "passive"))
    )
    (net (code "22") (name "Net-(5V6-PadC)") (class "Default")
      (node (ref "5V6") (pin "C") (pinfunction "C_C") (pintype "passive"))
      (node (ref "LED5_J6") (pin "2") (pinfunction "2_2") (pintype "passive"))
    )
    (net (code "23") (name "Net-(5V7-PadA)") (class "Default")
      (node (ref "5V7") (pin "A") (pinfunction "A_A") (pintype "passive"))
      (node (ref "R33") (pin "1") (pinfunction "1_1") (pintype "passive"))
    )
    (net (code "24") (name "Net-(5V7-PadC)") (class "Default")
      (node (ref "5V7") (pin "C") (pinfunction "C_C") (pintype "passive"))
      (node (ref "LED5_J7") (pin "2") (pinfunction "2_2") (pintype "passive"))
    )
    (net (code "25") (name "Net-(10UH1-Pad2)") (class "Default")
      (node (ref "10UH1") (pin "2") (pinfunction "2_2") (pintype "passive"))
      (node (ref "R_SENSE2") (pin "I2") (pinfunction "I2_I2") (pintype "bidirectional"))
    )
    (net (code "26") (name "Net-(C25-Pad1)") (class "Default")
      (node (ref "C25") (pin "1") (pinfunction "1_1") (pintype "passive"))
      (node (ref "R26") (pin "1") (pinfunction "1_1") (pintype "passive"))
    )
    (net (code "27") (name "Net-(C31-Pad1)") (class "Default")
      (node (ref "C31") (pin "1") (pinfunction "1_1") (pintype "passive"))
      (node (ref "C32") (pin "1") (pinfunction "1_1") (pintype "passive"))
      (node (ref "C34") (pin "1") (pinfunction "1_1") (pintype "passive"))
      (node (ref "R30") (pin "2") (pinfunction "2_2") (pintype "passive"))
      (node (ref "R_SENSE2") (pin "I1") (pinfunction "I1_I1") (pintype "bidirectional"))
    )
    (net (code "28") (name "Net-(C34-Pad2)") (class "Default")
      (node (ref "C34") (pin "2") (pinfunction "2_2") (pintype "passive"))
      (node (ref "R30") (pin "1") (pinfunction "1_1") (pintype "passive"))
      (node (ref "R31") (pin "2") (pinfunction "2_2") (pintype "passive"))
    )
    (net (code "29") (name "Net-(C38-Pad1)") (class "Default")
      (node (ref "C38") (pin "1") (pinfunction "1_1") (pintype "passive"))
      (node (ref "R35") (pin "1") (pinfunction "1_1") (pintype "passive"))
    )
    (net (code "30") (name "Net-(C100-Pad1)") (class "Default")
      (node (ref "C100") (pin "1") (pinfunction "1_1") (pintype "passive"))
      (node (ref "C101") (pin "1") (pinfunction "1_1") (pintype "passive"))
    )
    (net (code "31") (name "Net-(D1-PadA)") (class "Default")
      (node (ref "D1") (pin "A") (pinfunction "A_A") (pintype "passive"))
      (node (ref "R27") (pin "2") (pinfunction "2_2") (pintype "passive"))
      (node (ref "R35") (pin "2") (pinfunction "2_2") (pintype "passive"))
    )
    (net (code "32") (name "Net-(D2-A)") (class "Default")
      (node (ref "C33") (pin "1") (pinfunction "1_1") (pintype "passive"))
      (node (ref "D2") (pin "1") (pinfunction "A_1") (pintype "passive"))
      (node (ref "U1") (pin "12") (pinfunction "REGN_12") (pintype "power_in"))
    )
    (net (code "33") (name "Net-(D2-C)") (class "Default")
      (node (ref "C36") (pin "2") (pinfunction "2_2") (pintype "passive"))
      (node (ref "D2") (pin "3") (pinfunction "C_3") (pintype "passive"))
      (node (ref "U1") (pin "16") (pinfunction "BTST_16") (pintype "power_in"))
    )
    (net (code "34") (name "Net-(IC1A-+IN)") (class "Default")
      (node (ref "IC1") (pin "3") (pinfunction "+IN_3") (pintype "input"))
      (node (ref "R103") (pin "1") (pinfunction "1_1") (pintype "passive"))
      (node (ref "R104") (pin "2") (pinfunction "2_2") (pintype "passive"))
    )
    (net (code "35") (name "Net-(IC1A--IN)") (class "Default")
      (node (ref "IC1") (pin "2") (pinfunction "-IN_2") (pintype "input"))
      (node (ref "R107") (pin "1") (pinfunction "1_1") (pintype "passive"))
      (node (ref "R108") (pin "2") (pinfunction "2_2") (pintype "passive"))
    )
    (net (code "36") (name "Net-(IC1A-OUT)") (class "Default")
      (node (ref "IC1") (pin "1") (pinfunction "OUT_1") (pintype "output"))
      (node (ref "R108") (pin "1") (pinfunction "1_1") (pintype "passive"))
      (node (ref "R17") (pin "2") (pinfunction "2_2") (pintype "passive"))
    )
    (net (code "37") (name "Net-(IC1B-+IN)") (class "Default")
      (node (ref "IC1") (pin "5") (pinfunction "+IN_5") (pintype "input"))
      (node (ref "R116") (pin "1") (pinfunction "1_1") (pintype "passive"))
      (node (ref "R117") (pin "2") (pinfunction "2_2") (pintype "passive"))
    )
    (net (code "38") (name "Net-(IC1B--IN)") (class "Default")
      (node (ref "IC1") (pin "6") (pinfunction "-IN_6") (pintype "input"))
      (node (ref "R118") (pin "1") (pinfunction "1_1") (pintype "passive"))
      (node (ref "R119") (pin "2") (pinfunction "2_2") (pintype "passive"))
    )
    (net (code "39") (name "Net-(IC1B-OUT)") (class "Default")
      (node (ref "IC1") (pin "7") (pinfunction "OUT_7") (pintype "output"))
      (node (ref "R119") (pin "1") (pinfunction "1_1") (pintype "passive"))
      (node (ref "R13") (pin "2") (pinfunction "2_2") (pintype "passive"))
    )
    (net (code "40") (name "Net-(L1-1)") (class "Default")
      (node (ref "C10") (pin "1") (pinfunction "1_1") (pintype "passive"))
      (node (ref "L1") (pin "P$1") (pinfunction "1_P$1") (pintype "passive"))
      (node (ref "R7") (pin "2") (pinfunction "2_2") (pintype "passive"))
    )
    (net (code "41") (name "Net-(L1-2)") (class "Default")
      (node (ref "L1") (pin "P$2") (pinfunction "2_P$2") (pintype "passive"))
      (node (ref "U6") (pin "1") (pinfunction "SW_1") (pintype "power_in"))
      (node (ref "U6") (pin "2") (pinfunction "SW_2") (pintype "power_in"))
    )
    (net (code "42") (name "Net-(L2-1)") (class "Default")
      (node (ref "L2") (pin "P$1") (pinfunction "1_P$1") (pintype "passive"))
      (node (ref "U2") (pin "3") (pinfunction "L1_3") (pintype "passive"))
    )
    (net (code "43") (name "Net-(L2-2)") (class "Default")
      (node (ref "L2") (pin "P$2") (pinfunction "2_P$2") (pintype "passive"))
      (node (ref "U2") (pin "1") (pinfunction "L2_1") (pintype "passive"))
    )
    (net (code "44") (name "Net-(L3-1)") (class "Default")
      (node (ref "L3") (pin "P$1") (pinfunction "1_P$1") (pintype "passive"))
      (node (ref "U3") (pin "3") (pinfunction "L1_3") (pintype "passive"))
    )
    (net (code "45") (name "Net-(L3-2)") (class "Default")
      (node (ref "L3") (pin "P$2") (pinfunction "2_P$2") (pintype "passive"))
      (node (ref "U3") (pin "1") (pinfunction "L2_1") (pintype "passive"))
    )
    (net (code "46") (name "Net-(L4-1)") (class "Default")
      (node (ref "L4") (pin "P$1") (pinfunction "1_P$1") (pintype "passive"))
      (node (ref "U4") (pin "3") (pinfunction "L1_3") (pintype "passive"))
    )
    (net (code "47") (name "Net-(L4-2)") (class "Default")
      (node (ref "L4") (pin "P$2") (pinfunction "2_P$2") (pintype "passive"))
      (node (ref "U4") (pin "1") (pinfunction "L2_1") (pintype "passive"))
    )
    (net (code "48") (name "Net-(LED5_J-Pad2)") (class "Default")
      (node (ref "LED5_J") (pin "2") (pinfunction "2_2") (pintype "passive"))
      (node (ref "R6") (pin "1") (pinfunction "1_1") (pintype "passive"))
    )
    (net (code "49") (name "Net-(LED5_J1-Pad2)") (class "Default")
      (node (ref "LED5_J1") (pin "2") (pinfunction "2_2") (pintype "passive"))
      (node (ref "R16") (pin "1") (pinfunction "1_1") (pintype "passive"))
    )
    (net (code "50") (name "Net-(LED5_J2-Pad2)") (class "Default")
      (node (ref "LED5_J2") (pin "2") (pinfunction "2_2") (pintype "passive"))
      (node (ref "R18") (pin "1") (pinfunction "1_1") (pintype "passive"))
    )
    (net (code "51") (name "Net-(LED5_J3-Pad2)") (class "Default")
      (node (ref "LED5_J3") (pin "2") (pinfunction "2_2") (pintype "passive"))
      (node (ref "R19") (pin "1") (pinfunction "1_1") (pintype "passive"))
    )
    (net (code "52") (name "Net-(LED5_J4-Pad2)") (class "Default")
      (node (ref "LED5_J4") (pin "2") (pinfunction "2_2") (pintype "passive"))
      (node (ref "R20") (pin "1") (pinfunction "1_1") (pintype "passive"))
    )
    (net (code "53") (name "Net-(LED5_J5-Pad2)") (class "Default")
      (node (ref "LED5_J5") (pin "2") (pinfunction "2_2") (pintype "passive"))
      (node (ref "R21") (pin "1") (pinfunction "1_1") (pintype "passive"))
    )
    (net (code "54") (name "Net-(Q1-G)") (class "Default")
      (node (ref "Q1") (pin "1") (pinfunction "G_1") (pintype "passive"))
      (node (ref "R10") (pin "1") (pinfunction "1_1") (pintype "passive"))
    )
    (net (code "55") (name "Net-(Q2-G)") (class "Default")
      (node (ref "Q2") (pin "1") (pinfunction "G_1") (pintype "passive"))
      (node (ref "R9") (pin "1") (pinfunction "1_1") (pintype "passive"))
    )
    (net (code "56") (name "Net-(Q3-1)") (class "Default")
      (node (ref "Q3") (pin "P1") (pinfunction "1_P1") (pintype "bidirectional"))
      (node (ref "U8") (pin "6") (pinfunction "XIN/P2.6_6") (pintype "bidirectional"))
    )
    (net (code "57") (name "Net-(Q3-2)") (class "Default")
      (node (ref "Q3") (pin "P2") (pinfunction "2_P2") (pintype "bidirectional"))
      (node (ref "U8") (pin "5") (pinfunction "XOUT/P2.7_5") (pintype "bidirectional"))
    )
    (net (code "58") (name "Net-(Q100-G)") (class "Default")
      (node (ref "Q100") (pin "1") (pinfunction "G_1") (pintype "passive"))
      (node (ref "R11") (pin "1") (pinfunction "1_1") (pintype "passive"))
    )
    (net (code "59") (name "Net-(U$1-BOOT)") (class "Default")
      (node (ref "C20") (pin "2") (pinfunction "2_2") (pintype "passive"))
      (node (ref "U$1") (pin "P$8") (pinfunction "BOOT_P$8") (pintype "bidirectional"))
    )
    (net (code "60") (name "Net-(U$1-COMP)") (class "Default")
      (node (ref "C24") (pin "1") (pinfunction "1_1") (pintype "passive"))
      (node (ref "R26") (pin "2") (pinfunction "2_2") (pintype "passive"))
      (node (ref "U$1") (pin "P$18") (pinfunction "COMP_P$18") (pintype "bidirectional"))
    )
    (net (code "61") (name "Net-(U$1-FB)") (class "Default")
      (node (ref "R23") (pin "1") (pinfunction "1_1") (pintype "passive"))
      (node (ref "R24") (pin "2") (pinfunction "2_2") (pintype "passive"))
      (node (ref "U$1") (pin "P$17") (pinfunction "FB_P$17") (pintype "bidirectional"))
    )
    (net (code "62") (name "Net-(U$1-FSW)") (class "Default")
      (node (ref "R22") (pin "1") (pinfunction "1_1") (pintype "passive"))
      (node (ref "U$1") (pin "P$3") (pinfunction "FSW_P$3") (pintype "bidirectional"))
    )
    (net (code "63") (name "Net-(U$1-ILIM)") (class "Default")
      (node (ref "R25") (pin "2") (pinfunction "2_2") (pintype "passive"))
      (node (ref "U$1") (pin "P$19") (pinfunction "ILIM_P$19") (pintype "bidirectional"))
    )
    (net (code "64") (name "Net-(U$1-SS)") (class "Default")
      (node (ref "C23") (pin "1") (pinfunction "1_1") (pintype "passive"))
      (node (ref "U$1") (pin "P$10") (pinfunction "SS_P$10") (pintype "bidirectional"))
    )
    (net (code "65") (name "Net-(U$1-SW1)") (class "Default")
      (node (ref "C20") (pin "1") (pinfunction "1_1") (pintype "passive"))
      (node (ref "R22") (pin "2") (pinfunction "2_2") (pintype "passive"))
      (node (ref "U$1") (pin "P$4") (pinfunction "SW1_P$4") (pintype "bidirectional"))
      (node (ref "U$1") (pin "P$5") (pinfunction "SW2_P$5") (pintype "bidirectional"))
      (node (ref "U$1") (pin "P$6") (pinfunction "SW3_P$6") (pintype "bidirectional"))
      (node (ref "U$1") (pin "P$7") (pinfunction "SW4_P$7") (pintype "bidirectional"))
    )
    (net (code "66") (name "Net-(U$1-VCC)") (class "Default")
      (node (ref "C22") (pin "1") (pinfunction "1_1") (pintype "passive"))
      (node (ref "U$1") (pin "P$1") (pinfunction "VCC_P$1") (pintype "bidirectional"))
    )
    (net (code "67") (name "Net-(U$1-VIN)") (class "Default")
      (node (ref "C21") (pin "1") (pinfunction "1_1") (pintype "passive"))
      (node (ref "C30") (pin "1") (pinfunction "1_1") (pintype "passive"))
      (node (ref "U$1") (pin "P$9") (pinfunction "VIN_P$9") (pintype "bidirectional"))
    )
    (net (code "68") (name "Net-(U$1-VOUT1)") (class "Default")
      (node (ref "C26") (pin "2") (pinfunction "2_2") (pintype "passive"))
      (node (ref "C27") (pin "2") (pinfunction "2_2") (pintype "passive"))
      (node (ref "C28") (pin "2") (pinfunction "2_2") (pintype "passive"))
      (node (ref "C29") (pin "2") (pinfunction "2_2") (pintype "passive"))
      (node (ref "R23") (pin "2") (pinfunction "2_2") (pintype "passive"))
      (node (ref "U$1") (pin "P$14") (pinfunction "VOUT1_P$14") (pintype "bidirectional"))
      (node (ref "U$1") (pin "P$15") (pinfunction "VOUT2_P$15") (pintype "bidirectional"))
      (node (ref "U$1") (pin "P$16") (pinfunction "VOUT3_P$16") (pintype "bidirectional"))
    )
    (net (code "69") (name "Net-(U$2-IN+)") (class "Default")
      (node (ref "RSENSE1") (pin "V1") (pinfunction "V1_V1") (pintype "bidirectional"))
      (node (ref "U$2") (pin "4") (pinfunction "IN+_4") (pintype "bidirectional"))
    )
    (net (code "70") (name "Net-(U$2-IN-)") (class "Default")
      (node (ref "RSENSE1") (pin "V2") (pinfunction "V2_V2") (pintype "bidirectional"))
      (node (ref "U$2") (pin "5") (pinfunction "IN-_5") (pintype "bidirectional"))
    )
    (net (code "71") (name "Net-(U$2-OUT)") (class "Default")
      (node (ref "R5") (pin "2") (pinfunction "2_2") (pintype "passive"))
      (node (ref "U$2") (pin "6") (pinfunction "OUT_6") (pintype "bidirectional"))
    )
    (net (code "72") (name "Net-(U$3-IN+)") (class "Default")
      (node (ref "R_SENSE1") (pin "V1") (pinfunction "V1_V1") (pintype "bidirectional"))
      (node (ref "U$3") (pin "4") (pinfunction "IN+_4") (pintype "bidirectional"))
    )
    (net (code "73") (name "Net-(U$3-IN-)") (class "Default")
      (node (ref "R_SENSE1") (pin "V2") (pinfunction "V2_V2") (pintype "bidirectional"))
      (node (ref "U$3") (pin "5") (pinfunction "IN-_5") (pintype "bidirectional"))
    )
    (net (code "74") (name "Net-(U$3-OUT)") (class "Default")
      (node (ref "R4") (pin "2") (pinfunction "2_2") (pintype "passive"))
      (node (ref "U$3") (pin "6") (pinfunction "OUT_6") (pintype "bidirectional"))
    )
    (net (code "75") (name "Net-(U$100-IN)") (class "Default")
      (node (ref "C100") (pin "2") (pinfunction "2_2") (pintype "passive"))
      (node (ref "U$100") (pin "2") (pinfunction "IN_2") (pintype "bidirectional"))
    )
    (net (code "76") (name "Net-(U1-HIDRV)") (class "Default")
      (node (ref "U1") (pin "15") (pinfunction "HIDRV_15") (pintype "output"))
      (node (ref "U7") (pin "4") (pinfunction "G_4") (pintype "passive"))
    )
    (net (code "77") (name "Net-(U1-LODRV)") (class "Default")
      (node (ref "U1") (pin "13") (pinfunction "LODRV_13") (pintype "output"))
      (node (ref "U9") (pin "4") (pinfunction "G_4") (pintype "passive"))
    )
    (net (code "78") (name "Net-(U1-MPPSET)") (class "Default")
      (node (ref "R27") (pin "1") (pinfunction "1_1") (pintype "passive"))
      (node (ref "R28") (pin "2") (pinfunction "2_2") (pintype "passive"))
      (node (ref "U1") (pin "2") (pinfunction "MPPSET_2") (pintype "input"))
    )
    (net (code "79") (name "Net-(U1-PH)") (class "Default")
      (node (ref "10UH1") (pin "1") (pinfunction "1_1") (pintype "passive"))
      (node (ref "C36") (pin "1") (pinfunction "1_1") (pintype "passive"))
      (node (ref "U1") (pin "14") (pinfunction "PH_14") (pintype "power_in"))
      (node (ref "U7") (pin "1") (pinfunction "S_2_1") (pintype "passive"))
      (node (ref "U7") (pin "2") (pinfunction "S_3_2") (pintype "passive"))
      (node (ref "U7") (pin "3") (pinfunction "S_3") (pintype "passive"))
      (node (ref "U9") (pin "5") (pinfunction "D_2_5") (pintype "passive"))
      (node (ref "U9") (pin "6") (pinfunction "D_3_6") (pintype "passive"))
      (node (ref "U9") (pin "7") (pinfunction "D_4_7") (pintype "passive"))
      (node (ref "U9") (pin "8") (pinfunction "D_8") (pintype "passive"))
    )
    (net (code "80") (name "Net-(U1-SRN)") (class "Default")
      (node (ref "C35") (pin "1") (pinfunction "1_1") (pintype "passive"))
      (node (ref "R_SENSE2") (pin "V1") (pinfunction "V1_V1") (pintype "bidirectional"))
      (node (ref "U1") (pin "9") (pinfunction "SRN_9") (pintype "input"))
    )
    (net (code "81") (name "Net-(U1-SRP)") (class "Default")
      (node (ref "C35") (pin "2") (pinfunction "2_2") (pintype "passive"))
      (node (ref "R_SENSE2") (pin "V2") (pinfunction "V2_V2") (pintype "bidirectional"))
      (node (ref "U1") (pin "10") (pinfunction "SRP_10") (pintype "bidirectional"))
    )
    (net (code "82") (name "Net-(U1-STAT1)") (class "Default")
      (node (ref "LED5_J7") (pin "1") (pinfunction "1_1") (pintype "passive"))
      (node (ref "U1") (pin "3") (pinfunction "STAT1_3") (pintype "output"))
    )
    (net (code "83") (name "Net-(U1-STAT2)") (class "Default")
      (node (ref "LED5_J6") (pin "1") (pinfunction "1_1") (pintype "passive"))
      (node (ref "U1") (pin "5") (pinfunction "STAT2_5") (pintype "output"))
    )
    (net (code "84") (name "Net-(U1-VCC)") (class "Default")
      (node (ref "C40") (pin "1") (pinfunction "1_1") (pintype "passive"))
      (node (ref "R29") (pin "1") (pinfunction "1_1") (pintype "passive"))
      (node (ref "U1") (pin "1") (pinfunction "VCC_1") (pintype "power_in"))
    )
    (net (code "85") (name "Net-(U1-VREF)") (class "Default")
      (node (ref "C39") (pin "1") (pinfunction "1_1") (pintype "passive"))
      (node (ref "U1") (pin "6") (pinfunction "VREF_6") (pintype "power_in"))
    )
    (net (code "86") (name "Net-(U2-EN)") (class "Default")
      (node (ref "C1") (pin "1") (pinfunction "1_1") (pintype "passive"))
      (node (ref "U2") (pin "4") (pinfunction "VIN_2_4") (pintype "power_in"))
      (node (ref "U2") (pin "5") (pinfunction "VIN_3_5") (pintype "power_in"))
      (node (ref "U2") (pin "6") (pinfunction "VIN_6") (pintype "power_in"))
      (node (ref "U2") (pin "7") (pinfunction "VINA_7") (pintype "power_in"))
      (node (ref "U2") (pin "8") (pinfunction "EN_8") (pintype "input"))
    )
    (net (code "87") (name "Net-(U2-FB)") (class "Default")
      (node (ref "5V2") (pin "A") (pinfunction "A_A") (pintype "passive"))
      (node (ref "C2") (pin "1") (pinfunction "1_1") (pintype "passive"))
      (node (ref "C3") (pin "1") (pinfunction "1_1") (pintype "passive"))
      (node (ref "R1") (pin "2") (pinfunction "2_2") (pintype "passive"))
      (node (ref "U2") (pin "11") (pinfunction "FB_11") (pintype "input"))
      (node (ref "U2") (pin "12") (pinfunction "VOUT_2_12") (pintype "power_in"))
      (node (ref "U2") (pin "13") (pinfunction "VOUT_3_13") (pintype "power_in"))
      (node (ref "U2") (pin "14") (pinfunction "VOUT_14") (pintype "power_in"))
      (node (ref "U5") (pin "2") (pinfunction "IN1_2") (pintype "bidirectional"))
      (node (ref "U5") (pin "3") (pinfunction "IN2_3") (pintype "bidirectional"))
    )
    (net (code "88") (name "Net-(U3-EN)") (class "Default")
      (node (ref "R2") (pin "1") (pinfunction "1_1") (pintype "passive"))
      (node (ref "U3") (pin "8") (pinfunction "EN_8") (pintype "input"))
    )
    (net (code "89") (name "Net-(U3-FB)") (class "Default")
      (node (ref "5V3") (pin "A") (pinfunction "A_A") (pintype "passive"))
      (node (ref "C5") (pin "1") (pinfunction "1_1") (pintype "passive"))
      (node (ref "C6") (pin "1") (pinfunction "1_1") (pintype "passive"))
      (node (ref "U3") (pin "11") (pinfunction "FB_11") (pintype "input"))
      (node (ref "U3") (pin "12") (pinfunction "VOUT_2_12") (pintype "power_in"))
      (node (ref "U3") (pin "13") (pinfunction "VOUT_3_13") (pintype "power_in"))
      (node (ref "U3") (pin "14") (pinfunction "VOUT_14") (pintype "power_in"))
    )
    (net (code "90") (name "Net-(U3-VIN)") (class "Default")
      (node (ref "C4") (pin "1") (pinfunction "1_1") (pintype "passive"))
      (node (ref "U3") (pin "4") (pinfunction "VIN_2_4") (pintype "power_in"))
      (node (ref "U3") (pin "5") (pinfunction "VIN_3_5") (pintype "power_in"))
      (node (ref "U3") (pin "6") (pinfunction "VIN_6") (pintype "power_in"))
      (node (ref "U3") (pin "7") (pinfunction "VINA_7") (pintype "power_in"))
    )
    (net (code "91") (name "Net-(U4-EN)") (class "Default")
      (node (ref "R3") (pin "1") (pinfunction "1_1") (pintype "passive"))
      (node (ref "U4") (pin "8") (pinfunction "EN_8") (pintype "input"))
    )
    (net (code "92") (name "Net-(U4-FB)") (class "Default")
      (node (ref "5V4") (pin "A") (pinfunction "A_A") (pintype "passive"))
      (node (ref "C8") (pin "1") (pinfunction "1_1") (pintype "passive"))
      (node (ref "C9") (pin "1") (pinfunction "1_1") (pintype "passive"))
      (node (ref "U4") (pin "11") (pinfunction "FB_11") (pintype "input"))
      (node (ref "U4") (pin "12") (pinfunction "VOUT_2_12") (pintype "power_in"))
      (node (ref "U4") (pin "13") (pinfunction "VOUT_3_13") (pintype "power_in"))
      (node (ref "U4") (pin "14") (pinfunction "VOUT_14") (pintype "power_in"))
    )
    (net (code "93") (name "Net-(U4-VIN)") (class "Default")
      (node (ref "C7") (pin "1") (pinfunction "1_1") (pintype "passive"))
      (node (ref "U4") (pin "4") (pinfunction "VIN_2_4") (pintype "power_in"))
      (node (ref "U4") (pin "5") (pinfunction "VIN_3_5") (pintype "power_in"))
      (node (ref "U4") (pin "6") (pinfunction "VIN_6") (pintype "power_in"))
      (node (ref "U4") (pin "7") (pinfunction "VINA_7") (pintype "power_in"))
    )
    (net (code "94") (name "Net-(U5-EN)") (class "Default")
      (node (ref "R1") (pin "1") (pinfunction "1_1") (pintype "passive"))
      (node (ref "U5") (pin "4") (pinfunction "EN_4") (pintype "bidirectional"))
    )
    (net (code "95") (name "Net-(U5-OUT1)") (class "Default")
      (node (ref "5V1") (pin "A") (pinfunction "A_A") (pintype "passive"))
      (node (ref "U5") (pin "6") (pinfunction "OUT1_6") (pintype "bidirectional"))
      (node (ref "U5") (pin "7") (pinfunction "OUT2_7") (pintype "bidirectional"))
      (node (ref "U5") (pin "8") (pinfunction "OUT3_8") (pintype "bidirectional"))
    )
    (net (code "96") (name "Net-(U6-EN)") (class "Default")
      (node (ref "R7") (pin "1") (pinfunction "1_1") (pintype "passive"))
      (node (ref "U6") (pin "9") (pinfunction "EN_9") (pintype "input"))
    )
    (net (code "97") (name "Net-(U6-PG)") (class "Default")
      (node (ref "R8") (pin "1") (pinfunction "1_1") (pintype "passive"))
      (node (ref "U6") (pin "5") (pinfunction "PG_5") (pintype "output"))
    )
    (net (code "98") (name "Net-(U6-SS)") (class "Default")
      (node (ref "C14") (pin "1") (pinfunction "1_1") (pintype "passive"))
      (node (ref "U6") (pin "6") (pinfunction "SS_6") (pintype "bidirectional"))
    )
    (net (code "99") (name "Net-(U7-D)") (class "Default")
      (node (ref "C37") (pin "2") (pinfunction "2_2") (pintype "passive"))
      (node (ref "D1") (pin "C") (pinfunction "C_C") (pintype "passive"))
      (node (ref "R29") (pin "2") (pinfunction "2_2") (pintype "passive"))
      (node (ref "U7") (pin "5") (pinfunction "D_2_5") (pintype "passive"))
      (node (ref "U7") (pin "6") (pinfunction "D_3_6") (pintype "passive"))
      (node (ref "U7") (pin "7") (pinfunction "D_4_7") (pintype "passive"))
      (node (ref "U7") (pin "8") (pinfunction "D_8") (pintype "passive"))
    )
    (net (code "100") (name "unconnected-(5V5-PadA)") (class "Default")
      (node (ref "5V5") (pin "A") (pinfunction "A_A") (pintype "passive"))
    )
    (net (code "101") (name "unconnected-(10UH-Pad1)") (class "Default")
      (node (ref "10UH") (pin "1") (pinfunction "1_1") (pintype "passive"))
    )
    (net (code "102") (name "unconnected-(10UH-Pad2)") (class "Default")
      (node (ref "10UH") (pin "2") (pinfunction "2_2") (pintype "passive"))
    )
    (net (code "103") (name "unconnected-(C19-Pad1)") (class "Default")
      (node (ref "C19") (pin "1") (pinfunction "1_1") (pintype "passive"))
    )
    (net (code "104") (name "unconnected-(C102-Pad1)") (class "Default")
      (node (ref "C102") (pin "1") (pinfunction "1_1") (pintype "passive"))
    )
    (net (code "105") (name "unconnected-(C103-Pad+)") (class "Default")
      (node (ref "C103") (pin "+") (pinfunction "+_+") (pintype "passive"))
    )
    (net (code "106") (name "unconnected-(C_IC1-Pad2)") (class "Default")
      (node (ref "C_IC1") (pin "2") (pinfunction "2_2") (pintype "passive"))
    )
    (net (code "107") (name "unconnected-(FERRITE-Pad1)") (class "Default")
      (node (ref "FERRITE") (pin "1") (pinfunction "1_1") (pintype "passive"))
    )
    (net (code "108") (name "unconnected-(FERRITE-Pad2)") (class "Default")
      (node (ref "FERRITE") (pin "2") (pinfunction "2_2") (pintype "passive"))
    )
    (net (code "109") (name "unconnected-(L5-1-PadP$1)") (class "Default")
      (node (ref "L5") (pin "P$1") (pinfunction "1_P$1") (pintype "passive"))
    )
    (net (code "110") (name "unconnected-(L5-2-PadP$2)") (class "Default")
      (node (ref "L5") (pin "P$2") (pinfunction "2_P$2") (pintype "passive"))
    )
    (net (code "111") (name "unconnected-(R32-Pad2)") (class "Default")
      (node (ref "R32") (pin "2") (pinfunction "2_2") (pintype "passive"))
    )
    (net (code "112") (name "unconnected-(R33-Pad2)") (class "Default")
      (node (ref "R33") (pin "2") (pinfunction "2_2") (pintype "passive"))
    )
    (net (code "113") (name "unconnected-(R103-Pad2)") (class "Default")
      (node (ref "R103") (pin "2") (pinfunction "2_2") (pintype "passive"))
    )
    (net (code "114") (name "unconnected-(R104-Pad1)") (class "Default")
      (node (ref "R104") (pin "1") (pinfunction "1_1") (pintype "passive"))
    )
    (net (code "115") (name "unconnected-(R107-Pad2)") (class "Default")
      (node (ref "R107") (pin "2") (pinfunction "2_2") (pintype "passive"))
    )
    (net (code "116") (name "unconnected-(R116-Pad2)") (class "Default")
      (node (ref "R116") (pin "2") (pinfunction "2_2") (pintype "passive"))
    )
    (net (code "117") (name "unconnected-(R117-Pad1)") (class "Default")
      (node (ref "R117") (pin "1") (pinfunction "1_1") (pintype "passive"))
    )
    (net (code "118") (name "unconnected-(R118-Pad2)") (class "Default")
      (node (ref "R118") (pin "2") (pinfunction "2_2") (pintype "passive"))
    )
    (net (code "119") (name "unconnected-(RSENSE1-PadI1)") (class "Default")
      (node (ref "RSENSE1") (pin "I1") (pinfunction "I1_I1") (pintype "bidirectional"))
    )
    (net (code "120") (name "unconnected-(RSENSE1-PadI2)") (class "Default")
      (node (ref "RSENSE1") (pin "I2") (pinfunction "I2_I2") (pintype "bidirectional"))
    )
    (net (code "121") (name "unconnected-(R_SENSE1-PadI1)") (class "Default")
      (node (ref "R_SENSE1") (pin "I1") (pinfunction "I1_I1") (pintype "bidirectional"))
    )
    (net (code "122") (name "unconnected-(R_SENSE1-PadI2)") (class "Default")
      (node (ref "R_SENSE1") (pin "I2") (pinfunction "I2_I2") (pintype "bidirectional"))
    )
    (net (code "123") (name "unconnected-(U$1-EN-PadP$2)") (class "Default")
      (node (ref "U$1") (pin "P$2") (pinfunction "EN_P$2") (pintype "bidirectional"))
    )
    (net (code "124") (name "unconnected-(U$1-MODE-PadP$13)") (class "Default")
      (node (ref "U$1") (pin "P$13") (pinfunction "MODE_P$13") (pintype "bidirectional"))
    )
    (net (code "125") (name "unconnected-(U$2-VCC-Pad3)") (class "Default")
      (node (ref "U$2") (pin "3") (pinfunction "VCC_3") (pintype "bidirectional"))
    )
    (net (code "126") (name "unconnected-(U$3-VCC-Pad3)") (class "Default")
      (node (ref "U$3") (pin "3") (pinfunction "VCC_3") (pintype "bidirectional"))
    )
    (net (code "127") (name "unconnected-(U$100-NC1-Pad1)") (class "Default")
      (node (ref "U$100") (pin "1") (pinfunction "NC1_1") (pintype "bidirectional"))
    )
    (net (code "128") (name "unconnected-(U$100-NC2-Pad3)") (class "Default")
      (node (ref "U$100") (pin "3") (pinfunction "NC2_3") (pintype "bidirectional"))
    )
    (net (code "129") (name "unconnected-(U$100-NC3-Pad5)") (class "Default")
      (node (ref "U$100") (pin "5") (pinfunction "NC3_5") (pintype "bidirectional"))
    )
    (net (code "130") (name "unconnected-(U$100-NC4-Pad7)") (class "Default")
      (node (ref "U$100") (pin "7") (pinfunction "NC4_7") (pintype "bidirectional"))
    )
    (net (code "131") (name "unconnected-(U$100-NC5-Pad8)") (class "Default")
      (node (ref "U$100") (pin "8") (pinfunction "NC5_8") (pintype "bidirectional"))
    )
    (net (code "132") (name "unconnected-(U1-TS-Pad4)") (class "Default")
      (node (ref "U1") (pin "4") (pinfunction "TS_4") (pintype "input"))
    )
    (net (code "133") (name "unconnected-(U1-VFB-Pad8)") (class "Default")
      (node (ref "U1") (pin "8") (pinfunction "VFB_8") (pintype "input"))
    )
    (net (code "134") (name "unconnected-(U5-OC-Pad5)") (class "Default")
      (node (ref "U5") (pin "5") (pinfunction "OC_5") (pintype "bidirectional"))
    )
    (net (code "135") (name "unconnected-(U6-HYS-Pad8)") (class "Default")
      (node (ref "U6") (pin "8") (pinfunction "HYS_8") (pintype "output"))
    )
    (net (code "136") (name "unconnected-(U6-VIN-Pad10)") (class "Default")
      (node (ref "U6") (pin "10") (pinfunction "VIN_10") (pintype "input"))
    )
    (net (code "137") (name "unconnected-(U8-AVCC-Pad16)") (class "Default")
      (node (ref "U8") (pin "16") (pinfunction "AVCC_16") (pintype "bidirectional"))
    )
    (net (code "138") (name "unconnected-(U8-AVSS-Pad15)") (class "Default")
      (node (ref "U8") (pin "15") (pinfunction "AVSS_15") (pintype "bidirectional"))
    )
    (net (code "139") (name "unconnected-(U8-DVCC-Pad2)") (class "Default")
      (node (ref "U8") (pin "2") (pinfunction "DVCC_2") (pintype "bidirectional"))
    )
    (net (code "140") (name "unconnected-(U8-DVSS-Pad4)") (class "Default")
      (node (ref "U8") (pin "4") (pinfunction "DVSS_4") (pintype "bidirectional"))
    )
    (net (code "141") (name "unconnected-(U8-P1.0{slash}TACLK{slash}ADC10CLK-Pad31)") (class "Default")
      (node (ref "U8") (pin "31") (pinfunction "P1.0/TACLK/ADC10CLK_31") (pintype "bidirectional"))
    )
    (net (code "142") (name "unconnected-(U8-P1.1{slash}TA0-Pad32)") (class "Default")
      (node (ref "U8") (pin "32") (pinfunction "P1.1/TA0_32") (pintype "bidirectional"))
    )
    (net (code "143") (name "unconnected-(U8-P1.2{slash}TA1-Pad33)") (class "Default")
      (node (ref "U8") (pin "33") (pinfunction "P1.2/TA1_33") (pintype "bidirectional"))
    )
    (net (code "144") (name "unconnected-(U8-P1.3{slash}TA2-Pad34)") (class "Default")
      (node (ref "U8") (pin "34") (pinfunction "P1.3/TA2_34") (pintype "bidirectional"))
    )
    (net (code "145") (name "unconnected-(U8-P1.4{slash}SMCLK{slash}TCK-Pad35)") (class "Default")
      (node (ref "U8") (pin "35") (pinfunction "P1.4/SMCLK/TCK_35") (pintype "bidirectional"))
    )
    (net (code "146") (name "unconnected-(U8-P1.5{slash}TA0{slash}TMS-Pad36)") (class "Default")
      (node (ref "U8") (pin "36") (pinfunction "P1.5/TA0/TMS_36") (pintype "bidirectional"))
    )
    (net (code "147") (name "unconnected-(U8-P1.6{slash}TA1{slash}TDI-Pad37)") (class "Default")
      (node (ref "U8") (pin "37") (pinfunction "P1.6/TA1/TDI_37") (pintype "bidirectional"))
    )
    (net (code "148") (name "unconnected-(U8-P1.7{slash}TA2{slash}TDO{slash}TDI-Pad38)") (class "Default")
      (node (ref "U8") (pin "38") (pinfunction "P1.7/TA2/TDO/TDI_38") (pintype "bidirectional"))
    )
    (net (code "149") (name "unconnected-(U8-P2.0{slash}ACLK{slash}A0-Pad8)") (class "Default")
      (node (ref "U8") (pin "8") (pinfunction "P2.0/ACLK/A0_8") (pintype "bidirectional"))
    )
    (net (code "150") (name "unconnected-(U8-P2.1{slash}TAINCLK{slash}SMCLK{slash}A1-Pad9)") (class "Default")
      (node (ref "U8") (pin "9") (pinfunction "P2.1/TAINCLK/SMCLK/A1_9") (pintype "bidirectional"))
    )
    (net (code "151") (name "unconnected-(U8-P2.2{slash}TA0{slash}A2-Pad10)") (class "Default")
      (node (ref "U8") (pin "10") (pinfunction "P2.2/TA0/A2_10") (pintype "bidirectional"))
    )
    (net (code "152") (name "unconnected-(U8-P2.3{slash}TA1{slash}A3{slash}VREF−{slash}VEREF--Pad29)") (class "Default")
      (node (ref "U8") (pin "29") (pinfunction "P2.3/TA1/A3/VREF−/VEREF-_29") (pintype "bidirectional"))
    )
    (net (code "153") (name "unconnected-(U8-P2.4{slash}TA2{slash}A4{slash}VREF+{slash}VEREF+-Pad30)") (class "Default")
      (node (ref "U8") (pin "30") (pinfunction "P2.4/TA2/A4/VREF+/VEREF+_30") (pintype "bidirectional"))
    )
    (net (code "154") (name "unconnected-(U8-P2.5{slash}ROSC-Pad3)") (class "Default")
      (node (ref "U8") (pin "3") (pinfunction "P2.5/ROSC_3") (pintype "bidirectional"))
    )
    (net (code "155") (name "unconnected-(U8-P3.0{slash}UCB0STE{slash}UCA0CLK{slash}A5-Pad11)") (class "Default")
      (node (ref "U8") (pin "11") (pinfunction "P3.0/UCB0STE/UCA0CLK/A5_11") (pintype "bidirectional"))
    )
    (net (code "156") (name "unconnected-(U8-P3.1{slash}UCB0SIMO{slash}UCB0SDA-Pad12)") (class "Default")
      (node (ref "U8") (pin "12") (pinfunction "P3.1/UCB0SIMO/UCB0SDA_12") (pintype "bidirectional"))
    )
    (net (code "157") (name "unconnected-(U8-P3.2{slash}UCB0SOMI{slash}UCB0SCL-Pad13)") (class "Default")
      (node (ref "U8") (pin "13") (pinfunction "P3.2/UCB0SOMI/UCB0SCL_13") (pintype "bidirectional"))
    )
    (net (code "158") (name "unconnected-(U8-P3.3{slash}UCB0CLK{slash}UCA0STE-Pad14)") (class "Default")
      (node (ref "U8") (pin "14") (pinfunction "P3.3/UCB0CLK/UCA0STE_14") (pintype "bidirectional"))
    )
    (net (code "159") (name "unconnected-(U8-P3.4{slash}UCA0TXD{slash}UCA0SIMO-Pad25)") (class "Default")
      (node (ref "U8") (pin "25") (pinfunction "P3.4/UCA0TXD/UCA0SIMO_25") (pintype "bidirectional"))
    )
    (net (code "160") (name "unconnected-(U8-P3.5{slash}UCA0RXD{slash}UCA0SOMI-Pad26)") (class "Default")
      (node (ref "U8") (pin "26") (pinfunction "P3.5/UCA0RXD/UCA0SOMI_26") (pintype "bidirectional"))
    )
    (net (code "161") (name "unconnected-(U8-P3.6{slash}A6-Pad27)") (class "Default")
      (node (ref "U8") (pin "27") (pinfunction "P3.6/A6_27") (pintype "bidirectional"))
    )
    (net (code "162") (name "unconnected-(U8-P3.7{slash}A7-Pad28)") (class "Default")
      (node (ref "U8") (pin "28") (pinfunction "P3.7/A7_28") (pintype "bidirectional"))
    )
    (net (code "163") (name "unconnected-(U8-P4.0{slash}TB0-Pad17)") (class "Default")
      (node (ref "U8") (pin "17") (pinfunction "P4.0/TB0_17") (pintype "bidirectional"))
    )
    (net (code "164") (name "unconnected-(U8-P4.1{slash}TB1-Pad18)") (class "Default")
      (node (ref "U8") (pin "18") (pinfunction "P4.1/TB1_18") (pintype "bidirectional"))
    )
    (net (code "165") (name "unconnected-(U8-P4.2{slash}TB2-Pad19)") (class "Default")
      (node (ref "U8") (pin "19") (pinfunction "P4.2/TB2_19") (pintype "bidirectional"))
    )
    (net (code "166") (name "unconnected-(U8-P4.3{slash}TB0{slash}A12-Pad20)") (class "Default")
      (node (ref "U8") (pin "20") (pinfunction "P4.3/TB0/A12_20") (pintype "bidirectional"))
    )
    (net (code "167") (name "unconnected-(U8-P4.4{slash}TB1{slash}A13-Pad21)") (class "Default")
      (node (ref "U8") (pin "21") (pinfunction "P4.4/TB1/A13_21") (pintype "bidirectional"))
    )
    (net (code "168") (name "unconnected-(U8-P4.5{slash}TB2{slash}A14-Pad22)") (class "Default")
      (node (ref "U8") (pin "22") (pinfunction "P4.5/TB2/A14_22") (pintype "bidirectional"))
    )
    (net (code "169") (name "unconnected-(U8-P4.6{slash}TBOUTH{slash}A15-Pad23)") (class "Default")
      (node (ref "U8") (pin "23") (pinfunction "P4.6/TBOUTH/A15_23") (pintype "bidirectional"))
    )
    (net (code "170") (name "unconnected-(U8-P4.7{slash}TBCLK-Pad24)") (class "Default")
      (node (ref "U8") (pin "24") (pinfunction "P4.7/TBCLK_24") (pintype "bidirectional"))
    )
    (net (code "171") (name "unconnected-(U8-RST{slash}NMI{slash}SBWTDIO-Pad7)") (class "Default")
      (node (ref "U8") (pin "7") (pinfunction "RST/NMI/SBWTDIO_7") (pintype "bidirectional"))
    )
    (net (code "172") (name "unconnected-(U8-TEST{slash}SBWTCK-Pad1)") (class "Default")
      (node (ref "U8") (pin "1") (pinfunction "TEST/SBWTCK_1") (pintype "bidirectional"))
    )
  )
)
